# zikzak-z80-2.net
KiCad netlist of a schematic drawn in EAGLE
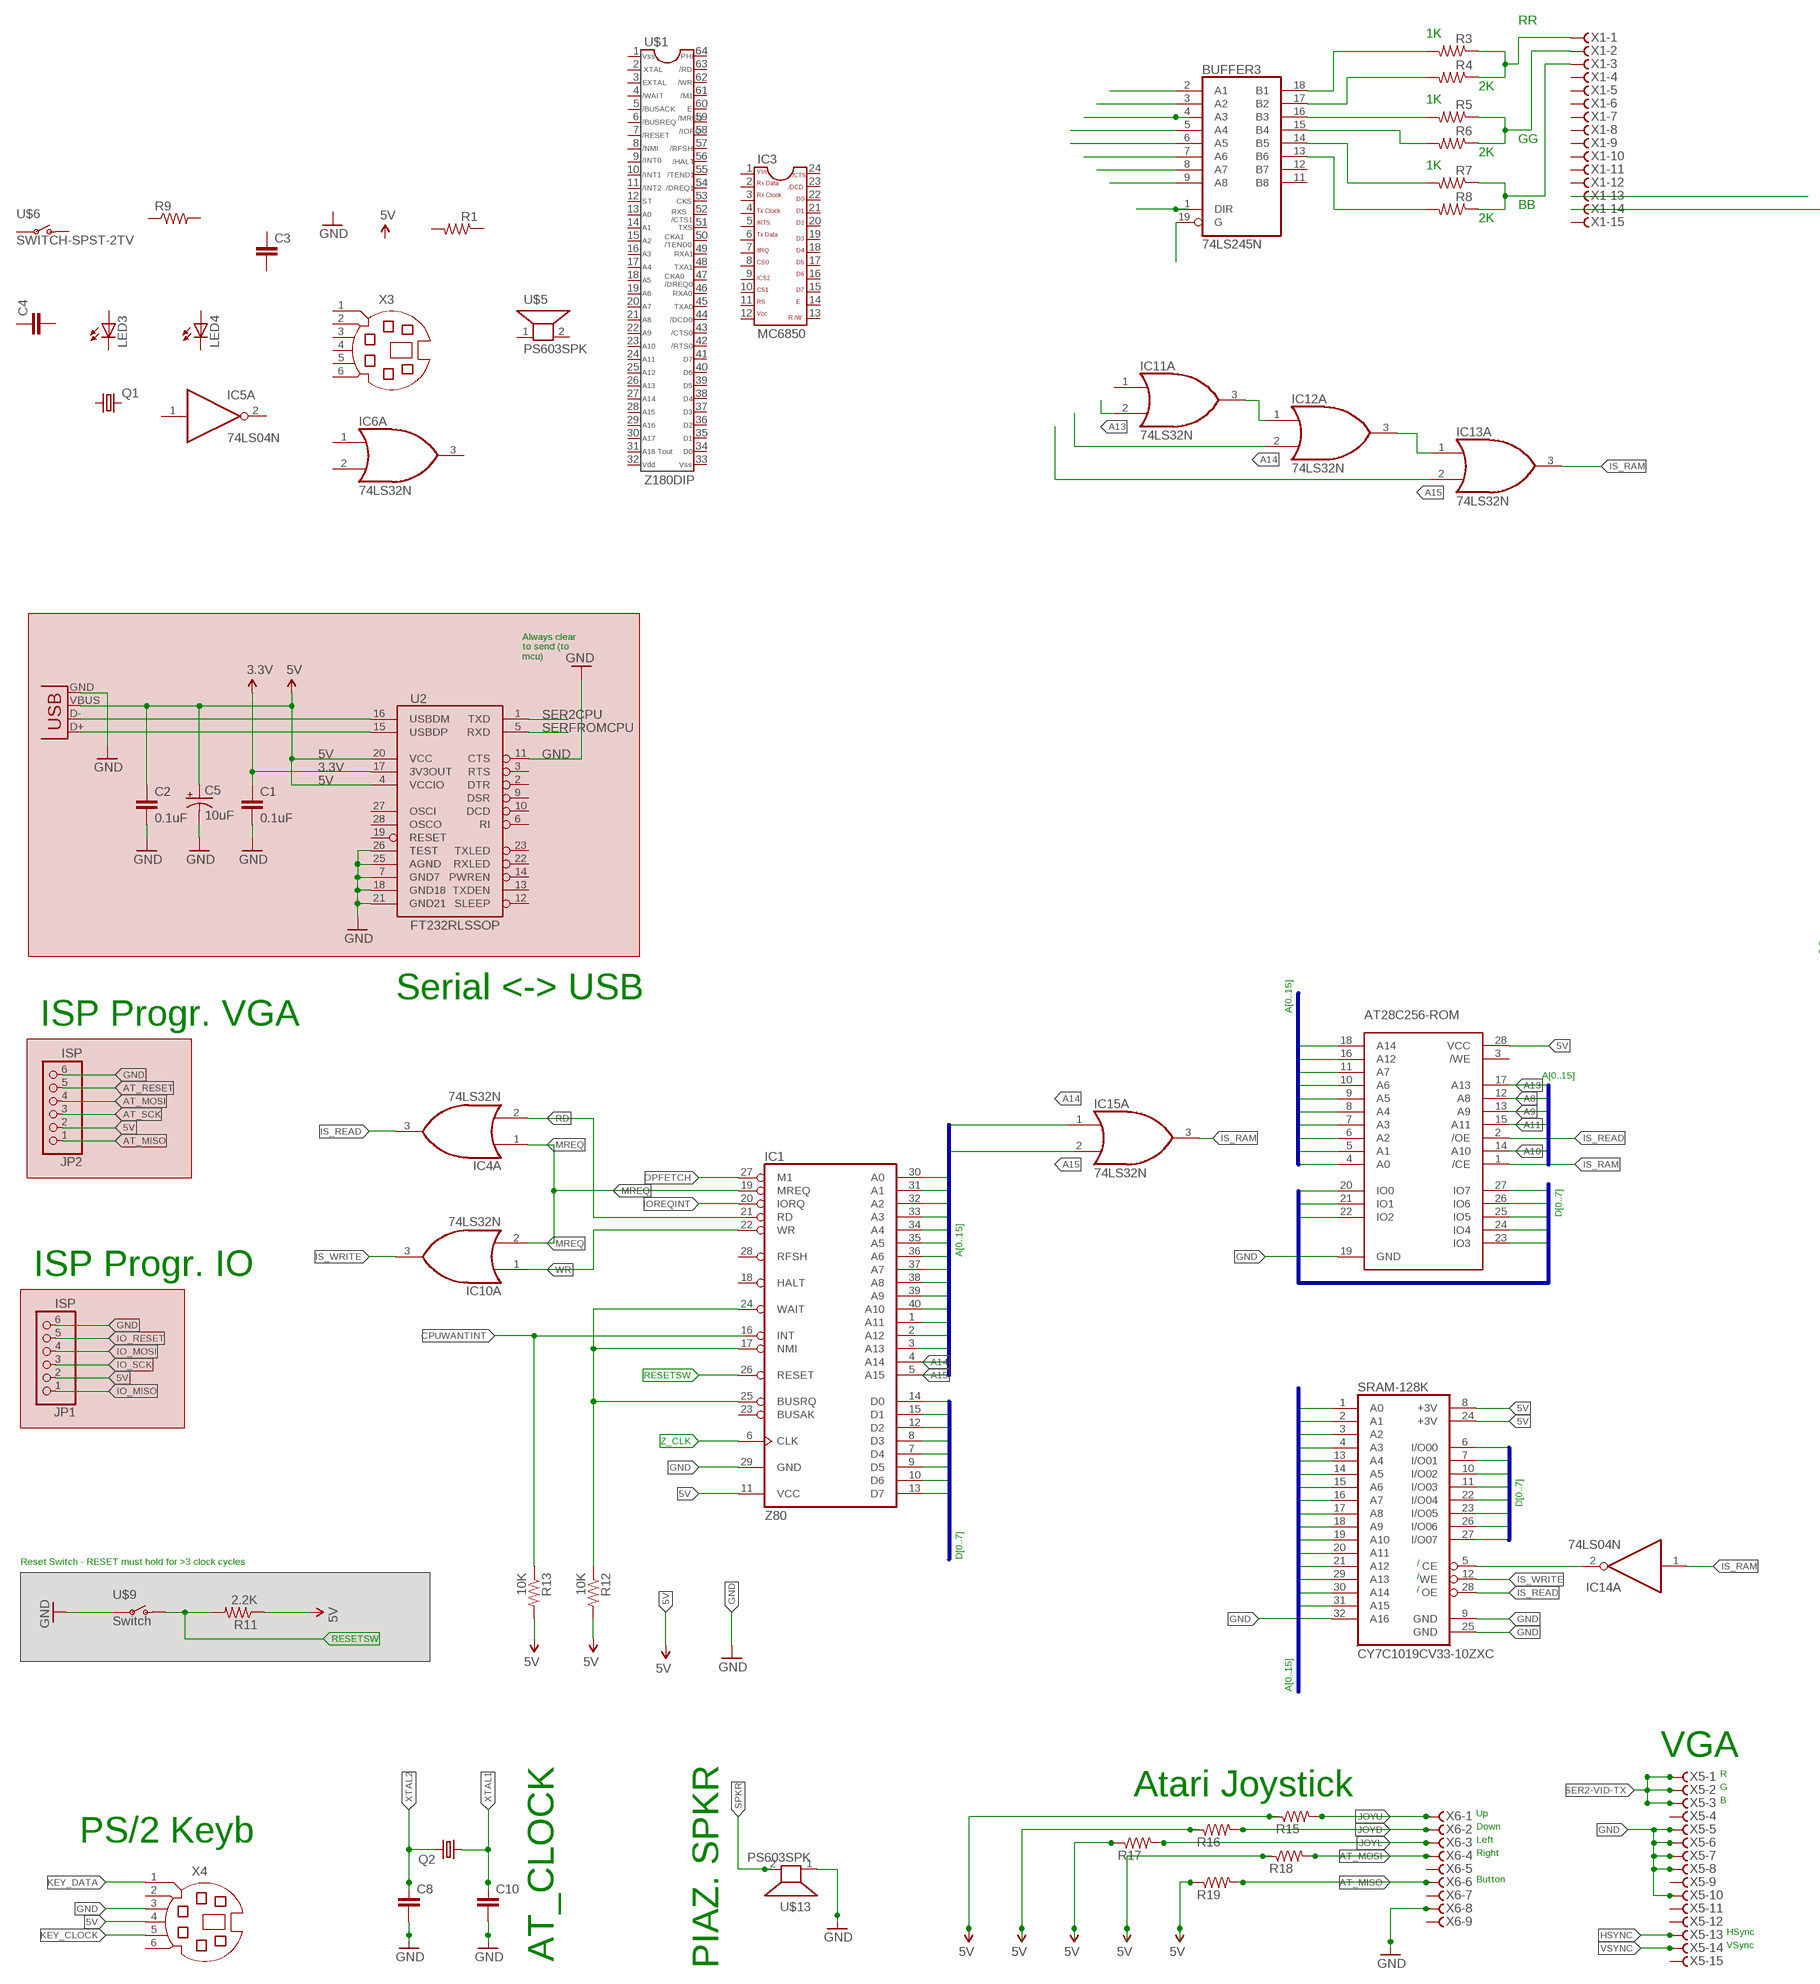
[diagram p0: schematic, sheet 1, part 1 of 2]
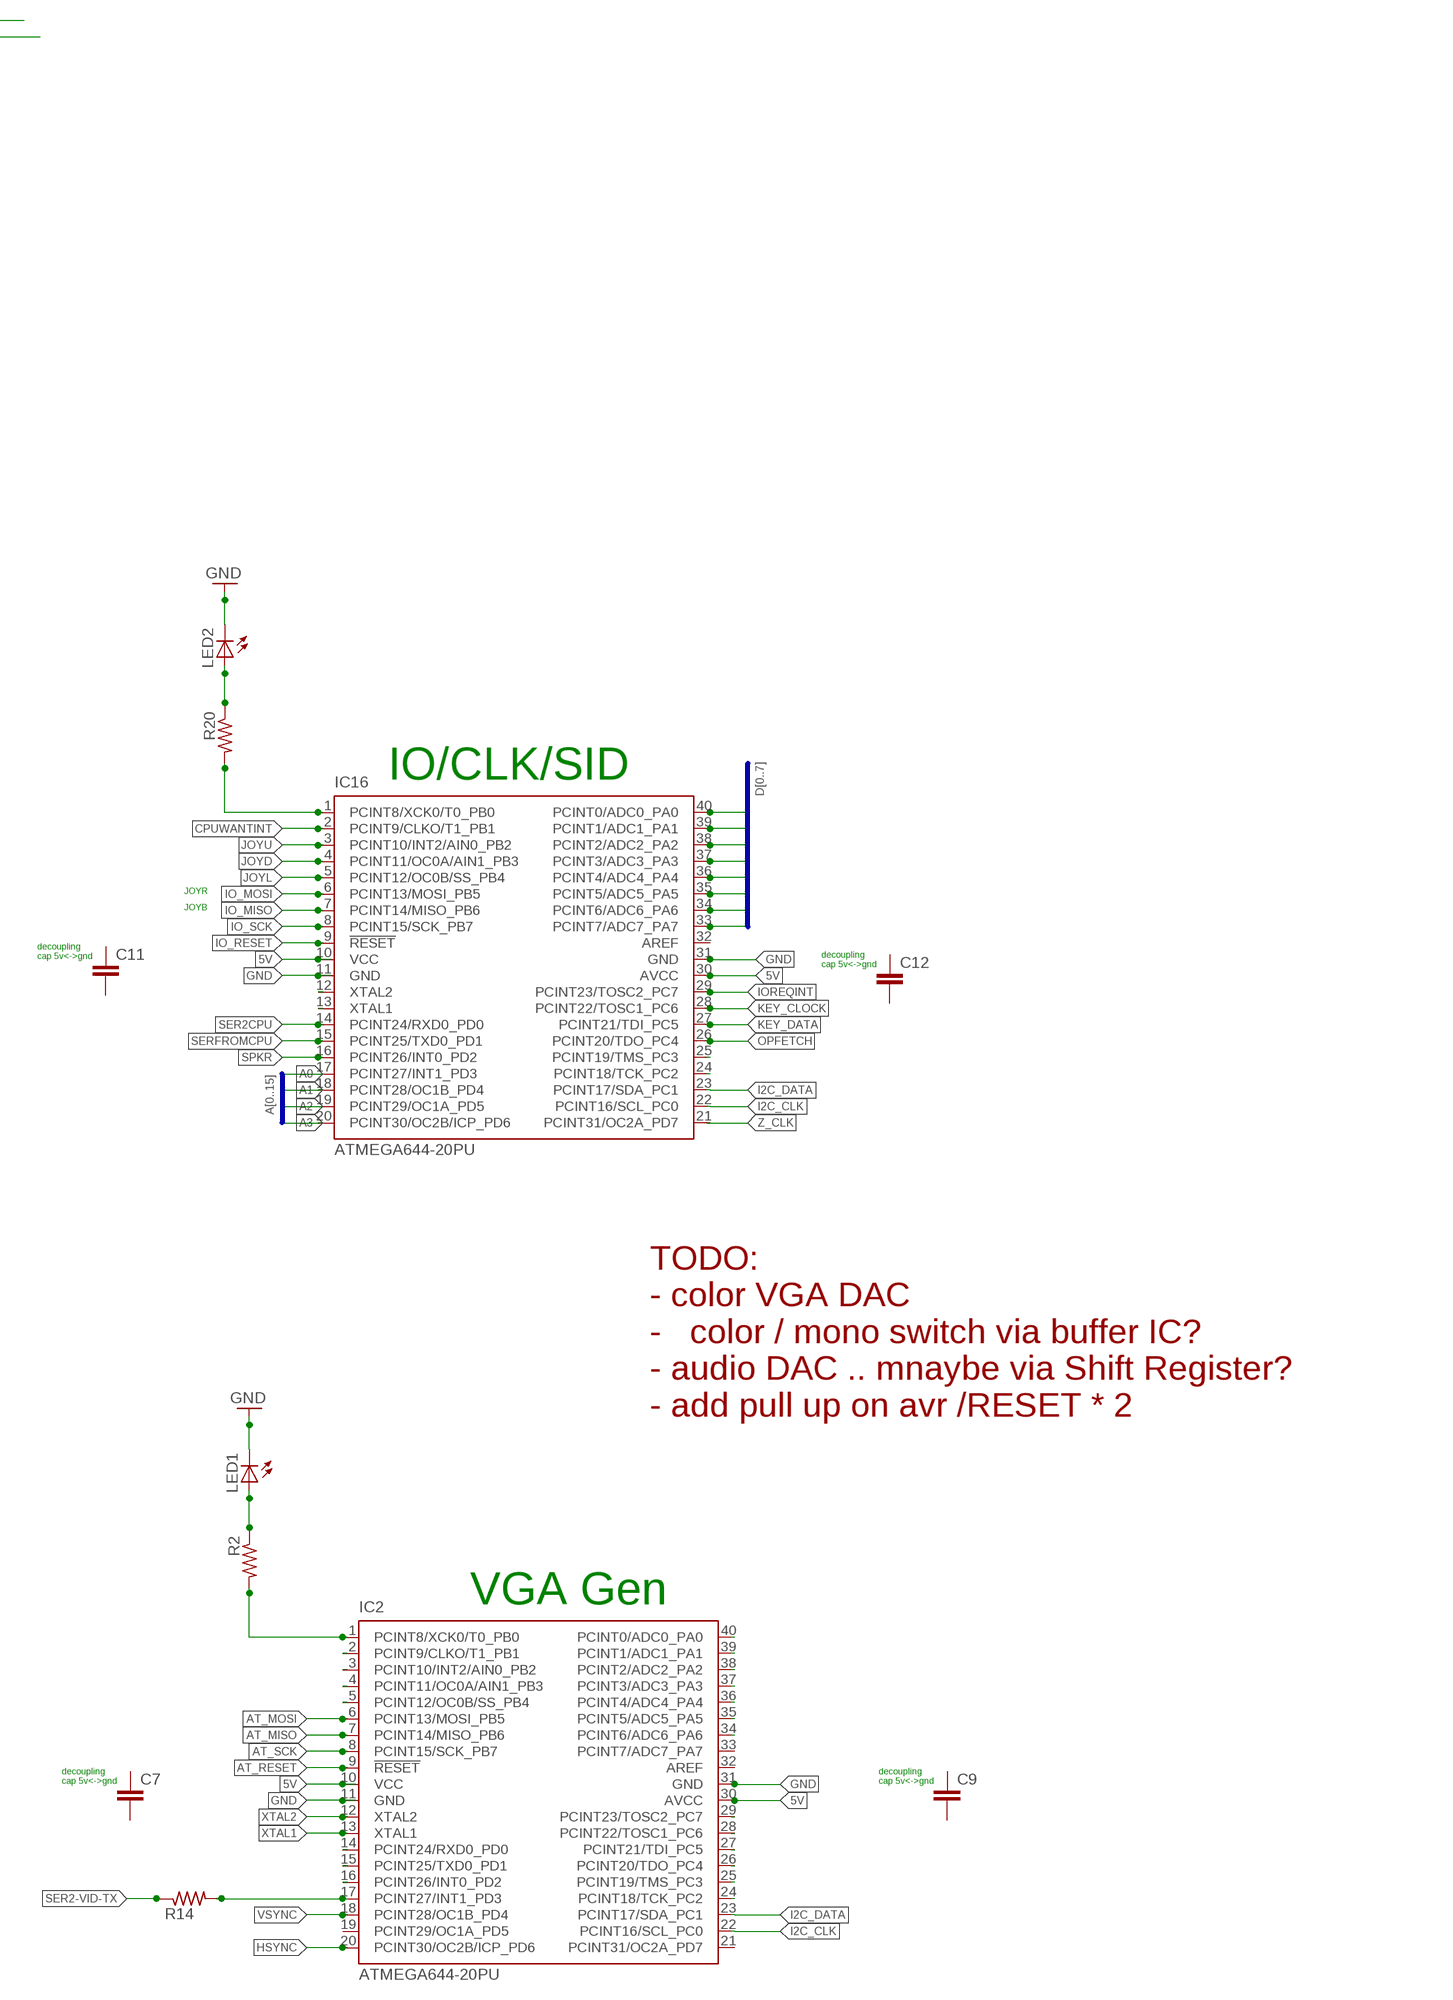
[diagram p1: schematic, sheet 1, part 2 of 2]

(export (version "E")
  (design (tool "Eeschema 10.0.6"))
  (components
    (comp (ref "AT28C256-ROM")
      (value "AT28C256")
      (footprint "eagle-import:DIL28-4")
      (libsource (lib "eagle-import") (part "AT28C256"))
    )
    (comp (ref "BUFFER3")
      (value "74LS245N")
      (footprint "eagle-import:DIL20")
      (libsource (lib "eagle-import") (part "74245NLS"))
    )
    (comp (ref "C1")
      (value "0.1uF")
      (footprint "eagle-import:0402-CAP")
      (libsource (lib "eagle-import") (part "CAP0402-CAP"))
    )
    (comp (ref "C2")
      (value "0.1uF")
      (footprint "eagle-import:0402-CAP")
      (libsource (lib "eagle-import") (part "CAP0402-CAP"))
    )
    (comp (ref "C3")
      (value "C-EU025-050X050")
      (footprint "eagle-import:C025-050X050")
      (libsource (lib "eagle-import") (part "C-EU025-050X050"))
    )
    (comp (ref "C4")
      (value "C-EUC0504")
      (footprint "eagle-import:C0504")
      (libsource (lib "eagle-import") (part "C-EUC0504"))
    )
    (comp (ref "C5")
      (value "10uF")
      (footprint "eagle-import:EIA3216")
      (libsource (lib "eagle-import") (part "CAP_POL1206"))
    )
    (comp (ref "C7")
      (value "C-EU025-050X050")
      (footprint "eagle-import:C025-050X050")
      (libsource (lib "eagle-import") (part "C-EU025-050X050"))
    )
    (comp (ref "C8")
      (value "C-EU025-050X050")
      (footprint "eagle-import:C025-050X050")
      (libsource (lib "eagle-import") (part "C-EU025-050X050"))
    )
    (comp (ref "C9")
      (value "C-EU025-050X050")
      (footprint "eagle-import:C025-050X050")
      (libsource (lib "eagle-import") (part "C-EU025-050X050"))
    )
    (comp (ref "C10")
      (value "C-EU025-050X050")
      (footprint "eagle-import:C025-050X050")
      (libsource (lib "eagle-import") (part "C-EU025-050X050"))
    )
    (comp (ref "C11")
      (value "C-EU025-050X050")
      (footprint "eagle-import:C025-050X050")
      (libsource (lib "eagle-import") (part "C-EU025-050X050"))
    )
    (comp (ref "C12")
      (value "C-EU025-050X050")
      (footprint "eagle-import:C025-050X050")
      (libsource (lib "eagle-import") (part "C-EU025-050X050"))
    )
    (comp (ref "IC1")
      (value "Z80")
      (footprint "eagle-import:DIL40")
      (libsource (lib "eagle-import") (part "Z80CPU"))
    )
    (comp (ref "IC2")
      (value "ATMEGA644-20PU")
      (footprint "eagle-import:DIL40")
      (libsource (lib "eagle-import") (part "ATMEGA644-PU20"))
    )
    (comp (ref "IC3")
      (value "MC6850")
      (footprint "eagle-import:DIL24-6")
      (libsource (lib "eagle-import") (part "MC6850-ACIA-6"))
    )
    (comp (ref "IC4")
      (value "74LS32N")
      (footprint "eagle-import:DIL14")
      (libsource (lib "eagle-import") (part "7432NLS"))
    )
    (comp (ref "IC5")
      (value "74LS04N")
      (footprint "eagle-import:DIL14")
      (libsource (lib "eagle-import") (part "7404NLS"))
    )
    (comp (ref "IC6")
      (value "74LS32N")
      (footprint "eagle-import:DIL14")
      (libsource (lib "eagle-import") (part "7432NLS"))
    )
    (comp (ref "IC10")
      (value "74LS32N")
      (footprint "eagle-import:DIL14")
      (libsource (lib "eagle-import") (part "7432NLS"))
    )
    (comp (ref "IC11")
      (value "74LS32N")
      (footprint "eagle-import:DIL14")
      (libsource (lib "eagle-import") (part "7432NLS"))
    )
    (comp (ref "IC12")
      (value "74LS32N")
      (footprint "eagle-import:DIL14")
      (libsource (lib "eagle-import") (part "7432NLS"))
    )
    (comp (ref "IC13")
      (value "74LS32N")
      (footprint "eagle-import:DIL14")
      (libsource (lib "eagle-import") (part "7432NLS"))
    )
    (comp (ref "IC14")
      (value "74LS04N")
      (footprint "eagle-import:DIL14")
      (libsource (lib "eagle-import") (part "7404NLS"))
    )
    (comp (ref "IC15")
      (value "74LS32N")
      (footprint "eagle-import:DIL14")
      (libsource (lib "eagle-import") (part "7432NLS"))
    )
    (comp (ref "IC16")
      (value "ATMEGA644-20PU")
      (footprint "eagle-import:DIL40")
      (libsource (lib "eagle-import") (part "ATMEGA644-PU20"))
    )
    (comp (ref "JP1")
      (value "ISP")
      (footprint "eagle-import:1X06")
      (libsource (lib "eagle-import") (part "PINHD-1X6"))
    )
    (comp (ref "JP2")
      (value "ISP")
      (footprint "eagle-import:1X06")
      (libsource (lib "eagle-import") (part "PINHD-1X6"))
    )
    (comp (ref "LED1")
      (value "LEDMINI-TOP")
      (footprint "eagle-import:OSRAM-MINI-TOP-LED")
      (libsource (lib "eagle-import") (part "LEDMINI-TOP"))
    )
    (comp (ref "LED2")
      (value "LEDMINI-TOP")
      (footprint "eagle-import:OSRAM-MINI-TOP-LED")
      (libsource (lib "eagle-import") (part "LEDMINI-TOP"))
    )
    (comp (ref "LED3")
      (value "LEDMINI-TOP")
      (footprint "eagle-import:OSRAM-MINI-TOP-LED")
      (libsource (lib "eagle-import") (part "LEDMINI-TOP"))
    )
    (comp (ref "LED4")
      (value "LEDMINI-TOP")
      (footprint "eagle-import:OSRAM-MINI-TOP-LED")
      (libsource (lib "eagle-import") (part "LEDMINI-TOP"))
    )
    (comp (ref "Q1")
      (value "CRYSTALHC49S")
      (footprint "eagle-import:HC49_S")
      (libsource (lib "eagle-import") (part "CRYSTALHC49S"))
    )
    (comp (ref "Q2")
      (value "CRYSTALHC49S")
      (footprint "eagle-import:HC49_S")
      (libsource (lib "eagle-import") (part "CRYSTALHC49S"))
    )
    (comp (ref "R1")
      (value "R-US_0204/2V")
      (footprint "eagle-import:0204V")
      (libsource (lib "eagle-import") (part "R-US_0204/2V"))
    )
    (comp (ref "R2")
      (value "R-US_0204/2V")
      (footprint "eagle-import:0204V")
      (libsource (lib "eagle-import") (part "R-US_0204/2V"))
    )
    (comp (ref "R3")
      (value "R-US_0204/2V")
      (footprint "eagle-import:0204V")
      (libsource (lib "eagle-import") (part "R-US_0204/2V"))
    )
    (comp (ref "R4")
      (value "R-US_0204/2V")
      (footprint "eagle-import:0204V")
      (libsource (lib "eagle-import") (part "R-US_0204/2V"))
    )
    (comp (ref "R5")
      (value "R-US_0204/2V")
      (footprint "eagle-import:0204V")
      (libsource (lib "eagle-import") (part "R-US_0204/2V"))
    )
    (comp (ref "R6")
      (value "R-US_0204/2V")
      (footprint "eagle-import:0204V")
      (libsource (lib "eagle-import") (part "R-US_0204/2V"))
    )
    (comp (ref "R7")
      (value "R-US_0204/2V")
      (footprint "eagle-import:0204V")
      (libsource (lib "eagle-import") (part "R-US_0204/2V"))
    )
    (comp (ref "R8")
      (value "R-US_0204/2V")
      (footprint "eagle-import:0204V")
      (libsource (lib "eagle-import") (part "R-US_0204/2V"))
    )
    (comp (ref "R9")
      (value "R-US_0204/7")
      (footprint "eagle-import:0204_7")
      (libsource (lib "eagle-import") (part "R-US_0204/7"))
    )
    (comp (ref "R11")
      (value "2.2K")
      (footprint "eagle-import:0204_7")
      (libsource (lib "eagle-import") (part "R-US_0204/7"))
    )
    (comp (ref "R12")
      (value "10K")
      (footprint "eagle-import:0204_7")
      (libsource (lib "eagle-import") (part "R-US_0204/7"))
    )
    (comp (ref "R13")
      (value "10K")
      (footprint "eagle-import:0204_7")
      (libsource (lib "eagle-import") (part "R-US_0204/7"))
    )
    (comp (ref "R14")
      (value "R-US_0204/2V")
      (footprint "eagle-import:0204V")
      (libsource (lib "eagle-import") (part "R-US_0204/2V"))
    )
    (comp (ref "R15")
      (value "R-US_0204/2V")
      (footprint "eagle-import:0204V")
      (libsource (lib "eagle-import") (part "R-US_0204/2V"))
    )
    (comp (ref "R16")
      (value "R-US_0204/2V")
      (footprint "eagle-import:0204V")
      (libsource (lib "eagle-import") (part "R-US_0204/2V"))
    )
    (comp (ref "R17")
      (value "R-US_0204/2V")
      (footprint "eagle-import:0204V")
      (libsource (lib "eagle-import") (part "R-US_0204/2V"))
    )
    (comp (ref "R18")
      (value "R-US_0204/2V")
      (footprint "eagle-import:0204V")
      (libsource (lib "eagle-import") (part "R-US_0204/2V"))
    )
    (comp (ref "R19")
      (value "R-US_0204/2V")
      (footprint "eagle-import:0204V")
      (libsource (lib "eagle-import") (part "R-US_0204/2V"))
    )
    (comp (ref "R20")
      (value "R-US_0204/2V")
      (footprint "eagle-import:0204V")
      (libsource (lib "eagle-import") (part "R-US_0204/2V"))
    )
    (comp (ref "SRAM-128K")
      (value "CY7C1019CV33-10ZXC")
      (footprint "eagle-import:TSOPII-32")
      (libsource (lib "eagle-import") (part "CY7C1019CV33ZXC-10"))
    )
    (comp (ref "U$1")
      (value "Z180DIP")
      (footprint "eagle-import:DIL64")
      (libsource (lib "eagle-import") (part "Z180DIP"))
    )
    (comp (ref "U$5")
      (value "PS603SPK")
      (footprint "eagle-import:PS603")
      (libsource (lib "eagle-import") (part "PS603SPK"))
    )
    (comp (ref "U$6")
      (value "SWITCH-SPST-2TV")
      (footprint "eagle-import:SWITCH-SPST-VERTICAL")
      (libsource (lib "eagle-import") (part "SWITCH-SPST-2TV"))
    )
    (comp (ref "U$9")
      (value "Switch")
      (footprint "eagle-import:SWITCH-SPST-VERTICAL")
      (libsource (lib "eagle-import") (part "SWITCH-SPST-2TV"))
    )
    (comp (ref "U$13")
      (value "PS603SPK")
      (footprint "eagle-import:PS603")
      (libsource (lib "eagle-import") (part "PS603SPK"))
    )
    (comp (ref "U2")
      (value "FT232RLSSOP")
      (footprint "eagle-import:SSOP28DB")
      (libsource (lib "eagle-import") (part "FT232RLSSOP"))
    )
    (comp (ref "X1")
      (value "F15HDVS")
      (footprint "eagle-import:HDF15V")
      (libsource (lib "eagle-import") (part "F15?SHDV"))
    )
    (comp (ref "X2")
      (value "USB-SMD-NS")
      (footprint "eagle-import:USB-MINIB-NOSTOP")
      (libsource (lib "eagle-import") (part "USB-SMD-NS"))
    )
    (comp (ref "X3")
      (value "MD06S")
      (footprint "eagle-import:MDIN06S")
      (libsource (lib "eagle-import") (part "MD06S"))
    )
    (comp (ref "X4")
      (value "MD06S")
      (footprint "eagle-import:MDIN06S")
      (libsource (lib "eagle-import") (part "MD06S"))
    )
    (comp (ref "X5")
      (value "F15HDVS")
      (footprint "eagle-import:HDF15V")
      (libsource (lib "eagle-import") (part "F15?SHDV"))
    )
    (comp (ref "X6")
      (value "F15HDVS")
      (footprint "eagle-import:HDF15V")
      (libsource (lib "eagle-import") (part "F15?SHDV"))
    )
  )
  (nets
    (net (code "1") (name "/A4") (class "Default")
      (node (ref "AT28C256-ROM") (pin "8") (pinfunction "A4_8") (pintype "input"))
      (node (ref "IC1") (pin "34") (pinfunction "A4_34") (pintype "output"))
      (node (ref "SRAM-128K") (pin "13") (pinfunction "A4_13") (pintype "input"))
    )
    (net (code "2") (name "/A5") (class "Default")
      (node (ref "AT28C256-ROM") (pin "9") (pinfunction "A5_9") (pintype "input"))
      (node (ref "IC1") (pin "35") (pinfunction "A5_35") (pintype "output"))
      (node (ref "SRAM-128K") (pin "14") (pinfunction "A5_14") (pintype "input"))
    )
    (net (code "3") (name "/A6") (class "Default")
      (node (ref "AT28C256-ROM") (pin "10") (pinfunction "A6_10") (pintype "input"))
      (node (ref "IC1") (pin "36") (pinfunction "A6_36") (pintype "output"))
      (node (ref "SRAM-128K") (pin "15") (pinfunction "A6_15") (pintype "input"))
    )
    (net (code "4") (name "/A7") (class "Default")
      (node (ref "AT28C256-ROM") (pin "11") (pinfunction "A7_11") (pintype "input"))
      (node (ref "IC1") (pin "37") (pinfunction "A7_37") (pintype "output"))
      (node (ref "SRAM-128K") (pin "16") (pinfunction "A7_16") (pintype "input"))
    )
    (net (code "5") (name "/A12") (class "Default")
      (node (ref "AT28C256-ROM") (pin "16") (pinfunction "A12_16") (pintype "input"))
      (node (ref "SRAM-128K") (pin "21") (pinfunction "A12_21") (pintype "input"))
    )
    (net (code "7") (name "/D0") (class "Default")
      (node (ref "AT28C256-ROM") (pin "20") (pinfunction "IO0_20") (pintype "bidirectional"))
      (node (ref "IC1") (pin "14") (pinfunction "D0_14") (pintype "bidirectional"))
      (node (ref "IC2") (pin "40") (pinfunction "PCINT0/ADC0_PA0_40") (pintype "bidirectional"))
      (node (ref "SRAM-128K") (pin "6") (pinfunction "I/O00_6") (pintype "bidirectional"))
    )
    (net (code "8") (name "/D1") (class "Default")
      (node (ref "AT28C256-ROM") (pin "21") (pinfunction "IO1_21") (pintype "bidirectional"))
      (node (ref "IC1") (pin "15") (pinfunction "D1_15") (pintype "bidirectional"))
      (node (ref "IC2") (pin "39") (pinfunction "PCINT1/ADC1_PA1_39") (pintype "bidirectional"))
      (node (ref "SRAM-128K") (pin "7") (pinfunction "I/O01_7") (pintype "bidirectional"))
    )
    (net (code "9") (name "/D2") (class "Default")
      (node (ref "AT28C256-ROM") (pin "22") (pinfunction "IO2_22") (pintype "bidirectional"))
      (node (ref "IC1") (pin "12") (pinfunction "D2_12") (pintype "bidirectional"))
      (node (ref "IC2") (pin "38") (pinfunction "PCINT2/ADC2_PA2_38") (pintype "bidirectional"))
      (node (ref "SRAM-128K") (pin "10") (pinfunction "I/O02_10") (pintype "bidirectional"))
    )
    (net (code "10") (name "/D3") (class "Default")
      (node (ref "AT28C256-ROM") (pin "23") (pinfunction "IO3_23") (pintype "bidirectional"))
      (node (ref "IC1") (pin "8") (pinfunction "D3_8") (pintype "bidirectional"))
      (node (ref "IC2") (pin "37") (pinfunction "PCINT3/ADC3_PA3_37") (pintype "bidirectional"))
      (node (ref "SRAM-128K") (pin "11") (pinfunction "I/O03_11") (pintype "bidirectional"))
    )
    (net (code "11") (name "/D4") (class "Default")
      (node (ref "AT28C256-ROM") (pin "24") (pinfunction "IO4_24") (pintype "bidirectional"))
      (node (ref "IC1") (pin "7") (pinfunction "D4_7") (pintype "bidirectional"))
      (node (ref "IC2") (pin "36") (pinfunction "PCINT4/ADC4_PA4_36") (pintype "bidirectional"))
      (node (ref "SRAM-128K") (pin "22") (pinfunction "I/O04_22") (pintype "bidirectional"))
    )
    (net (code "12") (name "/D5") (class "Default")
      (node (ref "AT28C256-ROM") (pin "25") (pinfunction "IO5_25") (pintype "bidirectional"))
      (node (ref "IC1") (pin "9") (pinfunction "D5_9") (pintype "bidirectional"))
      (node (ref "IC2") (pin "35") (pinfunction "PCINT5/ADC5_PA5_35") (pintype "bidirectional"))
      (node (ref "SRAM-128K") (pin "23") (pinfunction "I/O05_23") (pintype "bidirectional"))
    )
    (net (code "13") (name "/D6") (class "Default")
      (node (ref "AT28C256-ROM") (pin "26") (pinfunction "IO6_26") (pintype "bidirectional"))
      (node (ref "IC1") (pin "10") (pinfunction "D6_10") (pintype "bidirectional"))
      (node (ref "IC2") (pin "34") (pinfunction "PCINT6/ADC6_PA6_34") (pintype "bidirectional"))
      (node (ref "SRAM-128K") (pin "26") (pinfunction "I/O06_26") (pintype "bidirectional"))
    )
    (net (code "14") (name "/D7") (class "Default")
      (node (ref "AT28C256-ROM") (pin "27") (pinfunction "IO7_27") (pintype "bidirectional"))
      (node (ref "IC1") (pin "13") (pinfunction "D7_13") (pintype "bidirectional"))
      (node (ref "SRAM-128K") (pin "27") (pinfunction "I/O07_27") (pintype "bidirectional"))
    )
    (net (code "16") (name "3.3V") (class "Default")
      (node (ref "C1") (pin "1") (pinfunction "1_1") (pintype "passive"))
      (node (ref "U2") (pin "17") (pinfunction "3V3OUT_17") (pintype "output"))
    )
    (net (code "17") (name "5V") (class "Default")
      (node (ref "AT28C256-ROM") (pin "28") (pinfunction "VCC_28") (pintype "power_in"))
      (node (ref "C2") (pin "1") (pinfunction "1_1") (pintype "passive"))
      (node (ref "C5") (pin "A") (pinfunction "+_A") (pintype "passive"))
      (node (ref "IC1") (pin "11") (pinfunction "VCC_11") (pintype "power_in"))
      (node (ref "IC16") (pin "10") (pinfunction "VCC_10") (pintype "power_in"))
      (node (ref "IC16") (pin "30") (pinfunction "AVCC_30") (pintype "power_in"))
      (node (ref "IC2") (pin "10") (pinfunction "VCC_10") (pintype "power_in"))
      (node (ref "IC2") (pin "30") (pinfunction "AVCC_30") (pintype "power_in"))
      (node (ref "JP1") (pin "2") (pinfunction "2_2") (pintype "passive"))
      (node (ref "JP2") (pin "2") (pinfunction "2_2") (pintype "passive"))
      (node (ref "R11") (pin "1") (pinfunction "1_1") (pintype "passive"))
      (node (ref "R12") (pin "2") (pinfunction "2_2") (pintype "passive"))
      (node (ref "R13") (pin "2") (pinfunction "2_2") (pintype "passive"))
      (node (ref "R15") (pin "1") (pinfunction "1_1") (pintype "passive"))
      (node (ref "R16") (pin "1") (pinfunction "1_1") (pintype "passive"))
      (node (ref "R17") (pin "1") (pinfunction "1_1") (pintype "passive"))
      (node (ref "R18") (pin "1") (pinfunction "1_1") (pintype "passive"))
      (node (ref "R19") (pin "1") (pinfunction "1_1") (pintype "passive"))
      (node (ref "SRAM-128K") (pin "24") (pinfunction "+3V_24") (pintype "power_in"))
      (node (ref "SRAM-128K") (pin "8") (pinfunction "+3V_8") (pintype "power_in"))
      (node (ref "U2") (pin "20") (pinfunction "VCC_20") (pintype "power_in"))
      (node (ref "U2") (pin "4") (pinfunction "VCCIO_4") (pintype "power_in"))
      (node (ref "X2") (pin "VBUS") (pinfunction "VBUS_VBUS") (pintype "bidirectional"))
      (node (ref "X4") (pin "4") (pinfunction "4_4") (pintype "passive"))
    )
    (net (code "18") (name "A0") (class "Default")
      (node (ref "AT28C256-ROM") (pin "4") (pinfunction "A0_4") (pintype "input"))
      (node (ref "IC1") (pin "30") (pinfunction "A0_30") (pintype "output"))
      (node (ref "IC16") (pin "17") (pinfunction "PCINT27/INT1_PD3_17") (pintype "bidirectional"))
      (node (ref "SRAM-128K") (pin "1") (pinfunction "A0_1") (pintype "input"))
    )
    (net (code "19") (name "A1") (class "Default")
      (node (ref "AT28C256-ROM") (pin "5") (pinfunction "A1_5") (pintype "input"))
      (node (ref "IC1") (pin "31") (pinfunction "A1_31") (pintype "output"))
      (node (ref "IC16") (pin "18") (pinfunction "PCINT28/OC1B_PD4_18") (pintype "bidirectional"))
      (node (ref "SRAM-128K") (pin "2") (pinfunction "A1_2") (pintype "input"))
    )
    (net (code "20") (name "A2") (class "Default")
      (node (ref "AT28C256-ROM") (pin "6") (pinfunction "A2_6") (pintype "input"))
      (node (ref "IC1") (pin "32") (pinfunction "A2_32") (pintype "output"))
      (node (ref "IC16") (pin "24") (pinfunction "PCINT18/TCK_PC2_24") (pintype "bidirectional"))
      (node (ref "IC2") (pin "24") (pinfunction "PCINT18/TCK_PC2_24") (pintype "bidirectional"))
      (node (ref "SRAM-128K") (pin "3") (pinfunction "A2_3") (pintype "input"))
    )
    (net (code "21") (name "A3") (class "Default")
      (node (ref "AT28C256-ROM") (pin "7") (pinfunction "A3_7") (pintype "input"))
      (node (ref "IC1") (pin "33") (pinfunction "A3_33") (pintype "output"))
      (node (ref "IC16") (pin "20") (pinfunction "PCINT30/OC2B/ICP_PD6_20") (pintype "bidirectional"))
      (node (ref "IC16") (pin "25") (pinfunction "PCINT19/TMS_PC3_25") (pintype "bidirectional"))
      (node (ref "IC2") (pin "25") (pinfunction "PCINT19/TMS_PC3_25") (pintype "bidirectional"))
      (node (ref "SRAM-128K") (pin "4") (pinfunction "A3_4") (pintype "input"))
    )
    (net (code "22") (name "A8") (class "Default")
      (node (ref "AT28C256-ROM") (pin "12") (pinfunction "A8_12") (pintype "input"))
      (node (ref "IC1") (pin "38") (pinfunction "A8_38") (pintype "output"))
      (node (ref "SRAM-128K") (pin "17") (pinfunction "A8_17") (pintype "input"))
    )
    (net (code "23") (name "A9") (class "Default")
      (node (ref "AT28C256-ROM") (pin "13") (pinfunction "A9_13") (pintype "input"))
      (node (ref "IC1") (pin "39") (pinfunction "A9_39") (pintype "output"))
      (node (ref "SRAM-128K") (pin "18") (pinfunction "A9_18") (pintype "input"))
    )
    (net (code "24") (name "A10") (class "Default")
      (node (ref "AT28C256-ROM") (pin "14") (pinfunction "A10_14") (pintype "input"))
      (node (ref "IC1") (pin "40") (pinfunction "A10_40") (pintype "output"))
      (node (ref "SRAM-128K") (pin "19") (pinfunction "A10_19") (pintype "input"))
    )
    (net (code "25") (name "A11") (class "Default")
      (node (ref "AT28C256-ROM") (pin "15") (pinfunction "A11_15") (pintype "input"))
      (node (ref "IC1") (pin "1") (pinfunction "A11_1") (pintype "output"))
      (node (ref "SRAM-128K") (pin "20") (pinfunction "A11_20") (pintype "input"))
    )
    (net (code "26") (name "A13") (class "Default")
      (node (ref "AT28C256-ROM") (pin "17") (pinfunction "A13_17") (pintype "input"))
      (node (ref "IC11") (pin "2") (pinfunction "I1_2") (pintype "input"))
      (node (ref "SRAM-128K") (pin "29") (pinfunction "A13_29") (pintype "input"))
    )
    (net (code "27") (name "A14") (class "Default")
      (node (ref "AT28C256-ROM") (pin "18") (pinfunction "A14_18") (pintype "input"))
      (node (ref "IC1") (pin "4") (pinfunction "A14_4") (pintype "output"))
      (node (ref "IC12") (pin "2") (pinfunction "I1_2") (pintype "input"))
      (node (ref "IC15") (pin "1") (pinfunction "I0_1") (pintype "input"))
      (node (ref "SRAM-128K") (pin "30") (pinfunction "A14_30") (pintype "input"))
    )
    (net (code "28") (name "A15") (class "Default")
      (node (ref "IC1") (pin "5") (pinfunction "A15_5") (pintype "output"))
      (node (ref "IC13") (pin "2") (pinfunction "I1_2") (pintype "input"))
      (node (ref "SRAM-128K") (pin "31") (pinfunction "A15_31") (pintype "input"))
    )
    (net (code "29") (name "AT_MISO") (class "Default")
      (node (ref "IC2") (pin "7") (pinfunction "PCINT14/MISO_PB6_7") (pintype "bidirectional"))
      (node (ref "JP2") (pin "1") (pinfunction "1_1") (pintype "passive"))
      (node (ref "R19") (pin "2") (pinfunction "2_2") (pintype "passive"))
      (node (ref "X6") (pin "6") (pinfunction "F_6") (pintype "passive"))
    )
    (net (code "30") (name "AT_MOSI") (class "Default")
      (node (ref "IC2") (pin "6") (pinfunction "PCINT13/MOSI_PB5_6") (pintype "bidirectional"))
      (node (ref "JP2") (pin "4") (pinfunction "4_4") (pintype "passive"))
      (node (ref "R18") (pin "2") (pinfunction "2_2") (pintype "passive"))
      (node (ref "X6") (pin "4") (pinfunction "F_4") (pintype "passive"))
    )
    (net (code "31") (name "AT_RESET") (class "Default")
      (node (ref "IC2") (pin "9") (pinfunction "~{RESET}_9") (pintype "input"))
      (node (ref "JP2") (pin "5") (pinfunction "5_5") (pintype "passive"))
    )
    (net (code "32") (name "AT_SCK") (class "Default")
      (node (ref "IC2") (pin "8") (pinfunction "PCINT15/SCK_PB7_8") (pintype "bidirectional"))
      (node (ref "JP2") (pin "3") (pinfunction "3_3") (pintype "passive"))
    )
    (net (code "33") (name "CPUWANTINT") (class "Default")
      (node (ref "IC16") (pin "2") (pinfunction "PCINT9/CLKO/T1_PB1_2") (pintype "bidirectional"))
      (node (ref "IC2") (pin "2") (pinfunction "PCINT9/CLKO/T1_PB1_2") (pintype "bidirectional"))
      (node (ref "R13") (pin "1") (pinfunction "1_1") (pintype "passive"))
    )
    (net (code "34") (name "GND") (class "Default")
      (node (ref "AT28C256-ROM") (pin "19") (pinfunction "GND_19") (pintype "power_in"))
      (node (ref "C1") (pin "2") (pinfunction "2_2") (pintype "passive"))
      (node (ref "C10") (pin "2") (pinfunction "2_2") (pintype "passive"))
      (node (ref "C2") (pin "2") (pinfunction "2_2") (pintype "passive"))
      (node (ref "C5") (pin "C") (pinfunction "-_C") (pintype "passive"))
      (node (ref "C8") (pin "2") (pinfunction "2_2") (pintype "passive"))
      (node (ref "IC1") (pin "29") (pinfunction "GND_29") (pintype "power_in"))
      (node (ref "IC16") (pin "11") (pinfunction "GND_11") (pintype "power_in"))
      (node (ref "IC16") (pin "31") (pinfunction "GND_31") (pintype "power_in"))
      (node (ref "IC2") (pin "11") (pinfunction "GND_11") (pintype "power_in"))
      (node (ref "IC2") (pin "31") (pinfunction "GND_31") (pintype "power_in"))
      (node (ref "JP1") (pin "6") (pinfunction "6_6") (pintype "passive"))
      (node (ref "JP2") (pin "6") (pinfunction "6_6") (pintype "passive"))
      (node (ref "LED1") (pin "C") (pinfunction "C_C") (pintype "passive"))
      (node (ref "LED2") (pin "C") (pinfunction "C_C") (pintype "passive"))
      (node (ref "SRAM-128K") (pin "25") (pinfunction "GND_25") (pintype "power_in"))
      (node (ref "SRAM-128K") (pin "32") (pinfunction "A16_32") (pintype "input"))
      (node (ref "SRAM-128K") (pin "9") (pinfunction "GND_9") (pintype "power_in"))
      (node (ref "U$13") (pin "1") (pinfunction "1_1") (pintype "passive"))
      (node (ref "U$9") (pin "2") (pinfunction "P_2") (pintype "passive"))
      (node (ref "U2") (pin "11") (pinfunction "CTS_11") (pintype "input"))
      (node (ref "U2") (pin "18") (pinfunction "GND18_18") (pintype "power_in"))
      (node (ref "U2") (pin "21") (pinfunction "GND21_21") (pintype "power_in"))
      (node (ref "U2") (pin "25") (pinfunction "AGND_25") (pintype "power_in"))
      (node (ref "U2") (pin "26") (pinfunction "TEST_26") (pintype "input"))
      (node (ref "U2") (pin "7") (pinfunction "GND7_7") (pintype "power_in"))
      (node (ref "X2") (pin "GND") (pinfunction "GND_GND") (pintype "bidirectional"))
      (node (ref "X4") (pin "3") (pinfunction "3_3") (pintype "passive"))
      (node (ref "X5") (pin "10") (pinfunction "F_10") (pintype "passive"))
      (node (ref "X5") (pin "5") (pinfunction "F_5") (pintype "passive"))
      (node (ref "X5") (pin "6") (pinfunction "F_6") (pintype "passive"))
      (node (ref "X5") (pin "7") (pinfunction "F_7") (pintype "passive"))
      (node (ref "X5") (pin "8") (pinfunction "F_8") (pintype "passive"))
      (node (ref "X6") (pin "8") (pinfunction "F_8") (pintype "passive"))
    )
    (net (code "35") (name "HSYNC") (class "Default")
      (node (ref "IC2") (pin "20") (pinfunction "PCINT30/OC2B/ICP_PD6_20") (pintype "bidirectional"))
      (node (ref "X5") (pin "13") (pinfunction "F_13") (pintype "passive"))
    )
    (net (code "36") (name "I2C_CLK") (class "Default")
      (node (ref "IC16") (pin "22") (pinfunction "PCINT16/SCL_PC0_22") (pintype "bidirectional"))
      (node (ref "IC2") (pin "22") (pinfunction "PCINT16/SCL_PC0_22") (pintype "bidirectional"))
    )
    (net (code "37") (name "I2C_DATA") (class "Default")
      (node (ref "IC16") (pin "23") (pinfunction "PCINT17/SDA_PC1_23") (pintype "bidirectional"))
      (node (ref "IC2") (pin "23") (pinfunction "PCINT17/SDA_PC1_23") (pintype "bidirectional"))
    )
    (net (code "38") (name "IOREQINT") (class "Default")
      (node (ref "IC1") (pin "20") (pinfunction "IORQ_20") (pintype "output"))
      (node (ref "IC16") (pin "29") (pinfunction "PCINT23/TOSC2_PC7_29") (pintype "bidirectional"))
      (node (ref "IC2") (pin "29") (pinfunction "PCINT23/TOSC2_PC7_29") (pintype "bidirectional"))
    )
    (net (code "39") (name "IO_MISO") (class "Default")
      (node (ref "IC16") (pin "7") (pinfunction "PCINT14/MISO_PB6_7") (pintype "bidirectional"))
      (node (ref "JP1") (pin "1") (pinfunction "1_1") (pintype "passive"))
    )
    (net (code "40") (name "IO_MOSI") (class "Default")
      (node (ref "IC16") (pin "6") (pinfunction "PCINT13/MOSI_PB5_6") (pintype "bidirectional"))
      (node (ref "JP1") (pin "4") (pinfunction "4_4") (pintype "passive"))
    )
    (net (code "41") (name "IO_RESET") (class "Default")
      (node (ref "IC16") (pin "9") (pinfunction "~{RESET}_9") (pintype "input"))
      (node (ref "JP1") (pin "5") (pinfunction "5_5") (pintype "passive"))
    )
    (net (code "42") (name "IO_SCK") (class "Default")
      (node (ref "IC16") (pin "8") (pinfunction "PCINT15/SCK_PB7_8") (pintype "bidirectional"))
      (node (ref "JP1") (pin "3") (pinfunction "3_3") (pintype "passive"))
    )
    (net (code "43") (name "IS_RAM") (class "Default")
      (node (ref "AT28C256-ROM") (pin "1") (pinfunction "/CE_1") (pintype "input"))
      (node (ref "IC13") (pin "3") (pinfunction "O_3") (pintype "output"))
      (node (ref "IC14") (pin "1") (pinfunction "I_1") (pintype "input"))
      (node (ref "IC15") (pin "3") (pinfunction "O_3") (pintype "output"))
    )
    (net (code "44") (name "IS_READ") (class "Default")
      (node (ref "AT28C256-ROM") (pin "2") (pinfunction "/OE_2") (pintype "input"))
      (node (ref "IC4") (pin "3") (pinfunction "O_3") (pintype "output"))
      (node (ref "SRAM-128K") (pin "28") (pinfunction "OE_28") (pintype "input"))
    )
    (net (code "45") (name "IS_WRITE") (class "Default")
      (node (ref "IC10") (pin "3") (pinfunction "O_3") (pintype "output"))
      (node (ref "SRAM-128K") (pin "12") (pinfunction "WE_12") (pintype "input"))
    )
    (net (code "46") (name "JOYD") (class "Default")
      (node (ref "IC16") (pin "4") (pinfunction "PCINT11/OC0A/AIN1_PB3_4") (pintype "bidirectional"))
      (node (ref "IC2") (pin "4") (pinfunction "PCINT11/OC0A/AIN1_PB3_4") (pintype "bidirectional"))
      (node (ref "R16") (pin "2") (pinfunction "2_2") (pintype "passive"))
      (node (ref "X6") (pin "2") (pinfunction "F_2") (pintype "passive"))
    )
    (net (code "47") (name "JOYL") (class "Default")
      (node (ref "IC16") (pin "5") (pinfunction "PCINT12/OC0B/SS_PB4_5") (pintype "bidirectional"))
      (node (ref "IC2") (pin "5") (pinfunction "PCINT12/OC0B/SS_PB4_5") (pintype "bidirectional"))
      (node (ref "R17") (pin "2") (pinfunction "2_2") (pintype "passive"))
      (node (ref "X6") (pin "3") (pinfunction "F_3") (pintype "passive"))
    )
    (net (code "48") (name "JOYU") (class "Default")
      (node (ref "IC16") (pin "3") (pinfunction "PCINT10/INT2/AIN0_PB2_3") (pintype "bidirectional"))
      (node (ref "IC2") (pin "3") (pinfunction "PCINT10/INT2/AIN0_PB2_3") (pintype "bidirectional"))
      (node (ref "R15") (pin "2") (pinfunction "2_2") (pintype "passive"))
      (node (ref "X6") (pin "1") (pinfunction "F_1") (pintype "passive"))
    )
    (net (code "49") (name "KEY_CLOCK") (class "Default")
      (node (ref "IC16") (pin "28") (pinfunction "PCINT22/TOSC1_PC6_28") (pintype "bidirectional"))
      (node (ref "IC2") (pin "28") (pinfunction "PCINT22/TOSC1_PC6_28") (pintype "bidirectional"))
      (node (ref "X4") (pin "5") (pinfunction "5_5") (pintype "passive"))
    )
    (net (code "50") (name "KEY_DATA") (class "Default")
      (node (ref "IC16") (pin "27") (pinfunction "PCINT21/TDI_PC5_27") (pintype "bidirectional"))
      (node (ref "IC2") (pin "27") (pinfunction "PCINT21/TDI_PC5_27") (pintype "bidirectional"))
      (node (ref "X4") (pin "1") (pinfunction "1_1") (pintype "passive"))
    )
    (net (code "51") (name "MREQ") (class "Default")
      (node (ref "IC1") (pin "19") (pinfunction "MREQ_19") (pintype "output"))
      (node (ref "IC10") (pin "2") (pinfunction "I1_2") (pintype "input"))
      (node (ref "IC4") (pin "1") (pinfunction "I0_1") (pintype "input"))
    )
    (net (code "52") (name "Net-(BUFFER3A-B1)") (class "Default")
      (node (ref "BUFFER3") (pin "18") (pinfunction "B1_18") (pintype "bidirectional"))
      (node (ref "R3") (pin "2") (pinfunction "2_2") (pintype "passive"))
    )
    (net (code "53") (name "Net-(BUFFER3A-B2)") (class "Default")
      (node (ref "BUFFER3") (pin "17") (pinfunction "B2_17") (pintype "bidirectional"))
      (node (ref "R4") (pin "2") (pinfunction "2_2") (pintype "passive"))
    )
    (net (code "54") (name "Net-(BUFFER3A-B3)") (class "Default")
      (node (ref "BUFFER3") (pin "16") (pinfunction "B3_16") (pintype "bidirectional"))
      (node (ref "R5") (pin "2") (pinfunction "2_2") (pintype "passive"))
    )
    (net (code "55") (name "Net-(BUFFER3A-B4)") (class "Default")
      (node (ref "BUFFER3") (pin "15") (pinfunction "B4_15") (pintype "bidirectional"))
      (node (ref "R6") (pin "2") (pinfunction "2_2") (pintype "passive"))
    )
    (net (code "56") (name "Net-(BUFFER3A-B5)") (class "Default")
      (node (ref "BUFFER3") (pin "14") (pinfunction "B5_14") (pintype "bidirectional"))
      (node (ref "R7") (pin "2") (pinfunction "2_2") (pintype "passive"))
    )
    (net (code "57") (name "Net-(BUFFER3A-B6)") (class "Default")
      (node (ref "BUFFER3") (pin "13") (pinfunction "B6_13") (pintype "bidirectional"))
      (node (ref "R8") (pin "2") (pinfunction "2_2") (pintype "passive"))
    )
    (net (code "58") (name "Net-(IC1-BUSRQ)") (class "Default")
      (node (ref "IC1") (pin "17") (pinfunction "NMI_17") (pintype "input"))
      (node (ref "IC1") (pin "24") (pinfunction "WAIT_24") (pintype "input"))
      (node (ref "IC1") (pin "25") (pinfunction "BUSRQ_25") (pintype "input"))
      (node (ref "R12") (pin "1") (pinfunction "1_1") (pintype "passive"))
    )
    (net (code "59") (name "Net-(IC2-PCINT8{slash}XCK0{slash}T0_PB0)") (class "Default")
      (node (ref "IC2") (pin "1") (pinfunction "PCINT8/XCK0/T0_PB0_1") (pintype "bidirectional"))
      (node (ref "R2") (pin "2") (pinfunction "2_2") (pintype "passive"))
    )
    (net (code "60") (name "Net-(IC2-PCINT27{slash}INT1_PD3)") (class "Default")
      (node (ref "IC2") (pin "17") (pinfunction "PCINT27/INT1_PD3_17") (pintype "bidirectional"))
      (node (ref "R14") (pin "2") (pinfunction "2_2") (pintype "passive"))
    )
    (net (code "61") (name "Net-(IC11A-O)") (class "Default")
      (node (ref "IC11") (pin "3") (pinfunction "O_3") (pintype "output"))
      (node (ref "IC12") (pin "1") (pinfunction "I0_1") (pintype "input"))
    )
    (net (code "62") (name "Net-(IC12A-O)") (class "Default")
      (node (ref "IC12") (pin "3") (pinfunction "O_3") (pintype "output"))
      (node (ref "IC13") (pin "1") (pinfunction "I0_1") (pintype "input"))
    )
    (net (code "63") (name "Net-(IC14A-O)") (class "Default")
      (node (ref "IC14") (pin "2") (pinfunction "O_2") (pintype "output"))
      (node (ref "SRAM-128K") (pin "5") (pinfunction "CE_5") (pintype "bidirectional"))
    )
    (net (code "64") (name "Net-(IC16-PCINT8{slash}XCK0{slash}T0_PB0)") (class "Default")
      (node (ref "IC16") (pin "1") (pinfunction "PCINT8/XCK0/T0_PB0_1") (pintype "bidirectional"))
      (node (ref "R20") (pin "2") (pinfunction "2_2") (pintype "passive"))
    )
    (net (code "65") (name "Net-(LED1-PadA)") (class "Default")
      (node (ref "LED1") (pin "A") (pinfunction "A_A") (pintype "passive"))
      (node (ref "R2") (pin "1") (pinfunction "1_1") (pintype "passive"))
    )
    (net (code "66") (name "Net-(LED2-PadA)") (class "Default")
      (node (ref "LED2") (pin "A") (pinfunction "A_A") (pintype "passive"))
      (node (ref "R20") (pin "1") (pinfunction "1_1") (pintype "passive"))
    )
    (net (code "67") (name "Net-(U2-USBDM)") (class "Default")
      (node (ref "U2") (pin "16") (pinfunction "USBDM_16") (pintype "bidirectional"))
      (node (ref "X2") (pin "D-") (pinfunction "D-_D-") (pintype "bidirectional"))
    )
    (net (code "68") (name "Net-(U2-USBDP)") (class "Default")
      (node (ref "U2") (pin "15") (pinfunction "USBDP_15") (pintype "bidirectional"))
      (node (ref "X2") (pin "D+") (pinfunction "D+_D+") (pintype "bidirectional"))
    )
    (net (code "69") (name "Net-(X1A-F)") (class "Default")
      (node (ref "R3") (pin "1") (pinfunction "1_1") (pintype "passive"))
      (node (ref "R4") (pin "1") (pinfunction "1_1") (pintype "passive"))
      (node (ref "X1") (pin "1") (pinfunction "F_1") (pintype "passive"))
    )
    (net (code "70") (name "Net-(X1H-F)") (class "Default")
      (node (ref "R5") (pin "1") (pinfunction "1_1") (pintype "passive"))
      (node (ref "R6") (pin "1") (pinfunction "1_1") (pintype "passive"))
      (node (ref "X1") (pin "2") (pinfunction "F_2") (pintype "passive"))
    )
    (net (code "71") (name "Net-(X1I-F)") (class "Default")
      (node (ref "R7") (pin "1") (pinfunction "1_1") (pintype "passive"))
      (node (ref "R8") (pin "1") (pinfunction "1_1") (pintype "passive"))
      (node (ref "X1") (pin "3") (pinfunction "F_3") (pintype "passive"))
    )
    (net (code "72") (name "OPFETCH") (class "Default")
      (node (ref "IC1") (pin "27") (pinfunction "M1_27") (pintype "output"))
      (node (ref "IC16") (pin "26") (pinfunction "PCINT20/TDO_PC4_26") (pintype "bidirectional"))
      (node (ref "IC2") (pin "26") (pinfunction "PCINT20/TDO_PC4_26") (pintype "bidirectional"))
    )
    (net (code "73") (name "RD") (class "Default")
      (node (ref "IC1") (pin "21") (pinfunction "RD_21") (pintype "output"))
      (node (ref "IC4") (pin "2") (pinfunction "I1_2") (pintype "input"))
    )
    (net (code "74") (name "RESETSW") (class "Default")
      (node (ref "IC1") (pin "26") (pinfunction "RESET_26") (pintype "input"))
      (node (ref "R11") (pin "2") (pinfunction "2_2") (pintype "passive"))
      (node (ref "U$9") (pin "1") (pinfunction "O_1") (pintype "passive"))
    )
    (net (code "75") (name "SER2-VID-TX") (class "Default")
      (node (ref "R14") (pin "1") (pinfunction "1_1") (pintype "passive"))
      (node (ref "X5") (pin "1") (pinfunction "F_1") (pintype "passive"))
      (node (ref "X5") (pin "2") (pinfunction "F_2") (pintype "passive"))
      (node (ref "X5") (pin "3") (pinfunction "F_3") (pintype "passive"))
    )
    (net (code "76") (name "SER2CPU") (class "Default")
      (node (ref "IC16") (pin "14") (pinfunction "PCINT24/RXD0_PD0_14") (pintype "bidirectional"))
      (node (ref "IC2") (pin "14") (pinfunction "PCINT24/RXD0_PD0_14") (pintype "bidirectional"))
      (node (ref "U2") (pin "1") (pinfunction "TXD_1") (pintype "output"))
    )
    (net (code "77") (name "SERFROMCPU") (class "Default")
      (node (ref "IC16") (pin "15") (pinfunction "PCINT25/TXD0_PD1_15") (pintype "bidirectional"))
      (node (ref "IC2") (pin "15") (pinfunction "PCINT25/TXD0_PD1_15") (pintype "bidirectional"))
      (node (ref "U2") (pin "5") (pinfunction "RXD_5") (pintype "input"))
    )
    (net (code "78") (name "SPKR") (class "Default")
      (node (ref "IC16") (pin "16") (pinfunction "PCINT26/INT0_PD2_16") (pintype "bidirectional"))
      (node (ref "IC2") (pin "16") (pinfunction "PCINT26/INT0_PD2_16") (pintype "bidirectional"))
      (node (ref "U$13") (pin "2") (pinfunction "2_2") (pintype "passive"))
    )
    (net (code "79") (name "VSYNC") (class "Default")
      (node (ref "IC2") (pin "18") (pinfunction "PCINT28/OC1B_PD4_18") (pintype "bidirectional"))
      (node (ref "X5") (pin "14") (pinfunction "F_14") (pintype "passive"))
    )
    (net (code "80") (name "WR") (class "Default")
      (node (ref "IC1") (pin "22") (pinfunction "WR_22") (pintype "output"))
      (node (ref "IC10") (pin "1") (pinfunction "I0_1") (pintype "input"))
    )
    (net (code "81") (name "XTAL1") (class "Default")
      (node (ref "C10") (pin "1") (pinfunction "1_1") (pintype "passive"))
      (node (ref "IC16") (pin "13") (pinfunction "XTAL1_13") (pintype "input"))
      (node (ref "IC2") (pin "13") (pinfunction "XTAL1_13") (pintype "input"))
      (node (ref "Q2") (pin "1") (pinfunction "1_1") (pintype "passive"))
    )
    (net (code "82") (name "XTAL2") (class "Default")
      (node (ref "C8") (pin "1") (pinfunction "1_1") (pintype "passive"))
      (node (ref "IC16") (pin "12") (pinfunction "XTAL2_12") (pintype "output"))
      (node (ref "IC2") (pin "12") (pinfunction "XTAL2_12") (pintype "output"))
      (node (ref "Q2") (pin "2") (pinfunction "2_2") (pintype "passive"))
    )
    (net (code "83") (name "Z_CLK") (class "Default")
      (node (ref "IC1") (pin "6") (pinfunction "CLK_6") (pintype "input"))
    )
    (net (code "84") (name "unconnected-(AT28C256-ROM-{slash}WE-Pad3)") (class "Default")
      (node (ref "AT28C256-ROM") (pin "3") (pinfunction "/WE_3") (pintype "input"))
    )
    (net (code "85") (name "unconnected-(BUFFER3A-A1-Pad2)") (class "Default")
      (node (ref "BUFFER3") (pin "2") (pinfunction "A1_2") (pintype "bidirectional"))
    )
    (net (code "86") (name "unconnected-(BUFFER3A-A2-Pad3)") (class "Default")
      (node (ref "BUFFER3") (pin "3") (pinfunction "A2_3") (pintype "bidirectional"))
    )
    (net (code "87") (name "unconnected-(BUFFER3A-A3-Pad4)") (class "Default")
      (node (ref "BUFFER3") (pin "4") (pinfunction "A3_4") (pintype "bidirectional"))
    )
    (net (code "88") (name "unconnected-(BUFFER3A-A4-Pad5)") (class "Default")
      (node (ref "BUFFER3") (pin "5") (pinfunction "A4_5") (pintype "bidirectional"))
    )
    (net (code "89") (name "unconnected-(BUFFER3A-A5-Pad6)") (class "Default")
      (node (ref "BUFFER3") (pin "6") (pinfunction "A5_6") (pintype "bidirectional"))
    )
    (net (code "90") (name "unconnected-(BUFFER3A-A6-Pad7)") (class "Default")
      (node (ref "BUFFER3") (pin "7") (pinfunction "A6_7") (pintype "bidirectional"))
    )
    (net (code "91") (name "unconnected-(BUFFER3A-A7-Pad8)") (class "Default")
      (node (ref "BUFFER3") (pin "8") (pinfunction "A7_8") (pintype "bidirectional"))
    )
    (net (code "92") (name "unconnected-(BUFFER3A-A8-Pad9)") (class "Default")
      (node (ref "BUFFER3") (pin "9") (pinfunction "A8_9") (pintype "bidirectional"))
    )
    (net (code "93") (name "unconnected-(BUFFER3A-B7-Pad12)") (class "Default")
      (node (ref "BUFFER3") (pin "12") (pinfunction "B7_12") (pintype "bidirectional"))
    )
    (net (code "94") (name "unconnected-(BUFFER3A-B8-Pad11)") (class "Default")
      (node (ref "BUFFER3") (pin "11") (pinfunction "B8_11") (pintype "bidirectional"))
    )
    (net (code "95") (name "unconnected-(BUFFER3A-DIR-Pad1)") (class "Default")
      (node (ref "BUFFER3") (pin "1") (pinfunction "DIR_1") (pintype "input"))
    )
    (net (code "96") (name "unconnected-(BUFFER3A-G-Pad19)") (class "Default")
      (node (ref "BUFFER3") (pin "19") (pinfunction "G_19") (pintype "input"))
    )
    (net (code "97") (name "unconnected-(C3-Pad1)") (class "Default")
      (node (ref "C3") (pin "1") (pinfunction "1_1") (pintype "passive"))
    )
    (net (code "98") (name "unconnected-(C3-Pad2)") (class "Default")
      (node (ref "C3") (pin "2") (pinfunction "2_2") (pintype "passive"))
    )
    (net (code "99") (name "unconnected-(C4-Pad1)") (class "Default")
      (node (ref "C4") (pin "1") (pinfunction "1_1") (pintype "passive"))
    )
    (net (code "100") (name "unconnected-(C4-Pad2)") (class "Default")
      (node (ref "C4") (pin "2") (pinfunction "2_2") (pintype "passive"))
    )
    (net (code "101") (name "unconnected-(C7-Pad1)") (class "Default")
      (node (ref "C7") (pin "1") (pinfunction "1_1") (pintype "passive"))
    )
    (net (code "102") (name "unconnected-(C7-Pad2)") (class "Default")
      (node (ref "C7") (pin "2") (pinfunction "2_2") (pintype "passive"))
    )
    (net (code "103") (name "unconnected-(C9-Pad1)") (class "Default")
      (node (ref "C9") (pin "1") (pinfunction "1_1") (pintype "passive"))
    )
    (net (code "104") (name "unconnected-(C9-Pad2)") (class "Default")
      (node (ref "C9") (pin "2") (pinfunction "2_2") (pintype "passive"))
    )
    (net (code "105") (name "unconnected-(C11-Pad1)") (class "Default")
      (node (ref "C11") (pin "1") (pinfunction "1_1") (pintype "passive"))
    )
    (net (code "106") (name "unconnected-(C11-Pad2)") (class "Default")
      (node (ref "C11") (pin "2") (pinfunction "2_2") (pintype "passive"))
    )
    (net (code "107") (name "unconnected-(C12-Pad1)") (class "Default")
      (node (ref "C12") (pin "1") (pinfunction "1_1") (pintype "passive"))
    )
    (net (code "108") (name "unconnected-(C12-Pad2)") (class "Default")
      (node (ref "C12") (pin "2") (pinfunction "2_2") (pintype "passive"))
    )
    (net (code "109") (name "unconnected-(IC1-A12-Pad2)") (class "Default")
      (node (ref "IC1") (pin "2") (pinfunction "A12_2") (pintype "output"))
    )
    (net (code "110") (name "unconnected-(IC1-A13-Pad3)") (class "Default")
      (node (ref "IC1") (pin "3") (pinfunction "A13_3") (pintype "output"))
    )
    (net (code "111") (name "unconnected-(IC1-BUSAK-Pad23)") (class "Default")
      (node (ref "IC1") (pin "23") (pinfunction "BUSAK_23") (pintype "output"))
    )
    (net (code "112") (name "unconnected-(IC1-HALT-Pad18)") (class "Default")
      (node (ref "IC1") (pin "18") (pinfunction "HALT_18") (pintype "output"))
    )
    (net (code "113") (name "unconnected-(IC1-INT-Pad16)") (class "Default")
      (node (ref "IC1") (pin "16") (pinfunction "INT_16") (pintype "input"))
    )
    (net (code "114") (name "unconnected-(IC1-RFSH-Pad28)") (class "Default")
      (node (ref "IC1") (pin "28") (pinfunction "RFSH_28") (pintype "output"))
    )
    (net (code "115") (name "unconnected-(IC2-AREF-Pad32)") (class "Default")
      (node (ref "IC2") (pin "32") (pinfunction "AREF_32") (pintype "passive"))
    )
    (net (code "116") (name "unconnected-(IC2-PCINT7{slash}ADC7_PA7-Pad33)") (class "Default")
      (node (ref "IC2") (pin "33") (pinfunction "PCINT7/ADC7_PA7_33") (pintype "bidirectional"))
    )
    (net (code "117") (name "unconnected-(IC2-PCINT29{slash}OC1A_PD5-Pad19)") (class "Default")
      (node (ref "IC2") (pin "19") (pinfunction "PCINT29/OC1A_PD5_19") (pintype "bidirectional"))
    )
    (net (code "118") (name "unconnected-(IC2-PCINT31{slash}OC2A_PD7-Pad21)") (class "Default")
      (node (ref "IC2") (pin "21") (pinfunction "PCINT31/OC2A_PD7_21") (pintype "bidirectional"))
    )
    (net (code "119") (name "unconnected-(IC3-Pad1)") (class "Default")
      (node (ref "IC3") (pin "1") (pinfunction "1_1") (pintype "passive"))
    )
    (net (code "120") (name "unconnected-(IC3-Pad2)") (class "Default")
      (node (ref "IC3") (pin "2") (pinfunction "2_2") (pintype "passive"))
    )
    (net (code "121") (name "unconnected-(IC3-Pad3)") (class "Default")
      (node (ref "IC3") (pin "3") (pinfunction "3_3") (pintype "passive"))
    )
    (net (code "122") (name "unconnected-(IC3-Pad4)") (class "Default")
      (node (ref "IC3") (pin "4") (pinfunction "4_4") (pintype "passive"))
    )
    (net (code "123") (name "unconnected-(IC3-Pad5)") (class "Default")
      (node (ref "IC3") (pin "5") (pinfunction "5_5") (pintype "passive"))
    )
    (net (code "124") (name "unconnected-(IC3-Pad6)") (class "Default")
      (node (ref "IC3") (pin "6") (pinfunction "6_6") (pintype "passive"))
    )
    (net (code "125") (name "unconnected-(IC3-Pad7)") (class "Default")
      (node (ref "IC3") (pin "7") (pinfunction "7_7") (pintype "passive"))
    )
    (net (code "126") (name "unconnected-(IC3-Pad8)") (class "Default")
      (node (ref "IC3") (pin "8") (pinfunction "8_8") (pintype "passive"))
    )
    (net (code "127") (name "unconnected-(IC3-Pad9)") (class "Default")
      (node (ref "IC3") (pin "9") (pinfunction "9_9") (pintype "passive"))
    )
    (net (code "128") (name "unconnected-(IC3-Pad10)") (class "Default")
      (node (ref "IC3") (pin "10") (pinfunction "10_10") (pintype "passive"))
    )
    (net (code "129") (name "unconnected-(IC3-Pad11)") (class "Default")
      (node (ref "IC3") (pin "11") (pinfunction "11_11") (pintype "passive"))
    )
    (net (code "130") (name "unconnected-(IC3-Pad12)") (class "Default")
      (node (ref "IC3") (pin "12") (pinfunction "12_12") (pintype "passive"))
    )
    (net (code "131") (name "unconnected-(IC3-Pad13)") (class "Default")
      (node (ref "IC3") (pin "13") (pinfunction "13_13") (pintype "passive"))
    )
    (net (code "132") (name "unconnected-(IC3-Pad14)") (class "Default")
      (node (ref "IC3") (pin "14") (pinfunction "14_14") (pintype "passive"))
    )
    (net (code "133") (name "unconnected-(IC3-Pad15)") (class "Default")
      (node (ref "IC3") (pin "15") (pinfunction "15_15") (pintype "passive"))
    )
    (net (code "134") (name "unconnected-(IC3-Pad16)") (class "Default")
      (node (ref "IC3") (pin "16") (pinfunction "16_16") (pintype "passive"))
    )
    (net (code "135") (name "unconnected-(IC3-Pad17)") (class "Default")
      (node (ref "IC3") (pin "17") (pinfunction "17_17") (pintype "passive"))
    )
    (net (code "136") (name "unconnected-(IC3-Pad18)") (class "Default")
      (node (ref "IC3") (pin "18") (pinfunction "18_18") (pintype "passive"))
    )
    (net (code "137") (name "unconnected-(IC3-Pad19)") (class "Default")
      (node (ref "IC3") (pin "19") (pinfunction "19_19") (pintype "passive"))
    )
    (net (code "138") (name "unconnected-(IC3-Pad20)") (class "Default")
      (node (ref "IC3") (pin "20") (pinfunction "20_20") (pintype "passive"))
    )
    (net (code "139") (name "unconnected-(IC3-Pad21)") (class "Default")
      (node (ref "IC3") (pin "21") (pinfunction "21_21") (pintype "passive"))
    )
    (net (code "140") (name "unconnected-(IC3-Pad22)") (class "Default")
      (node (ref "IC3") (pin "22") (pinfunction "22_22") (pintype "passive"))
    )
    (net (code "141") (name "unconnected-(IC3-Pad23)") (class "Default")
      (node (ref "IC3") (pin "23") (pinfunction "23_23") (pintype "passive"))
    )
    (net (code "142") (name "unconnected-(IC3-Pad24)") (class "Default")
      (node (ref "IC3") (pin "24") (pinfunction "24_24") (pintype "passive"))
    )
    (net (code "143") (name "unconnected-(IC5A-I-Pad1)") (class "Default")
      (node (ref "IC5") (pin "1") (pinfunction "I_1") (pintype "input"))
    )
    (net (code "144") (name "unconnected-(IC5A-O-Pad2)") (class "Default")
      (node (ref "IC5") (pin "2") (pinfunction "O_2") (pintype "output"))
    )
    (net (code "145") (name "unconnected-(IC6A-I0-Pad1)") (class "Default")
      (node (ref "IC6") (pin "1") (pinfunction "I0_1") (pintype "input"))
    )
    (net (code "146") (name "unconnected-(IC6A-I1-Pad2)") (class "Default")
      (node (ref "IC6") (pin "2") (pinfunction "I1_2") (pintype "input"))
    )
    (net (code "147") (name "unconnected-(IC6A-O-Pad3)") (class "Default")
      (node (ref "IC6") (pin "3") (pinfunction "O_3") (pintype "output"))
    )
    (net (code "148") (name "unconnected-(IC11A-I0-Pad1)") (class "Default")
      (node (ref "IC11") (pin "1") (pinfunction "I0_1") (pintype "input"))
    )
    (net (code "149") (name "unconnected-(IC15A-I1-Pad2)") (class "Default")
      (node (ref "IC15") (pin "2") (pinfunction "I1_2") (pintype "input"))
    )
    (net (code "150") (name "unconnected-(IC16-AREF-Pad32)") (class "Default")
      (node (ref "IC16") (pin "32") (pinfunction "AREF_32") (pintype "passive"))
    )
    (net (code "151") (name "unconnected-(IC16-PCINT0{slash}ADC0_PA0-Pad40)") (class "Default")
      (node (ref "IC16") (pin "40") (pinfunction "PCINT0/ADC0_PA0_40") (pintype "bidirectional"))
    )
    (net (code "152") (name "unconnected-(IC16-PCINT1{slash}ADC1_PA1-Pad39)") (class "Default")
      (node (ref "IC16") (pin "39") (pinfunction "PCINT1/ADC1_PA1_39") (pintype "bidirectional"))
    )
    (net (code "153") (name "unconnected-(IC16-PCINT2{slash}ADC2_PA2-Pad38)") (class "Default")
      (node (ref "IC16") (pin "38") (pinfunction "PCINT2/ADC2_PA2_38") (pintype "bidirectional"))
    )
    (net (code "154") (name "unconnected-(IC16-PCINT3{slash}ADC3_PA3-Pad37)") (class "Default")
      (node (ref "IC16") (pin "37") (pinfunction "PCINT3/ADC3_PA3_37") (pintype "bidirectional"))
    )
    (net (code "155") (name "unconnected-(IC16-PCINT4{slash}ADC4_PA4-Pad36)") (class "Default")
      (node (ref "IC16") (pin "36") (pinfunction "PCINT4/ADC4_PA4_36") (pintype "bidirectional"))
    )
    (net (code "156") (name "unconnected-(IC16-PCINT5{slash}ADC5_PA5-Pad35)") (class "Default")
      (node (ref "IC16") (pin "35") (pinfunction "PCINT5/ADC5_PA5_35") (pintype "bidirectional"))
    )
    (net (code "157") (name "unconnected-(IC16-PCINT6{slash}ADC6_PA6-Pad34)") (class "Default")
      (node (ref "IC16") (pin "34") (pinfunction "PCINT6/ADC6_PA6_34") (pintype "bidirectional"))
    )
    (net (code "158") (name "unconnected-(IC16-PCINT7{slash}ADC7_PA7-Pad33)") (class "Default")
      (node (ref "IC16") (pin "33") (pinfunction "PCINT7/ADC7_PA7_33") (pintype "bidirectional"))
    )
    (net (code "159") (name "unconnected-(IC16-PCINT29{slash}OC1A_PD5-Pad19)") (class "Default")
      (node (ref "IC16") (pin "19") (pinfunction "PCINT29/OC1A_PD5_19") (pintype "bidirectional"))
    )
    (net (code "160") (name "unconnected-(IC16-PCINT31{slash}OC2A_PD7-Pad21)") (class "Default")
      (node (ref "IC16") (pin "21") (pinfunction "PCINT31/OC2A_PD7_21") (pintype "bidirectional"))
    )
    (net (code "161") (name "unconnected-(LED3-PadA)") (class "Default")
      (node (ref "LED3") (pin "A") (pinfunction "A_A") (pintype "passive"))
    )
    (net (code "162") (name "unconnected-(LED3-PadC)") (class "Default")
      (node (ref "LED3") (pin "C") (pinfunction "C_C") (pintype "passive"))
    )
    (net (code "163") (name "unconnected-(LED4-PadA)") (class "Default")
      (node (ref "LED4") (pin "A") (pinfunction "A_A") (pintype "passive"))
    )
    (net (code "164") (name "unconnected-(LED4-PadC)") (class "Default")
      (node (ref "LED4") (pin "C") (pinfunction "C_C") (pintype "passive"))
    )
    (net (code "165") (name "unconnected-(Q1-Pad1)") (class "Default")
      (node (ref "Q1") (pin "1") (pinfunction "1_1") (pintype "passive"))
    )
    (net (code "166") (name "unconnected-(Q1-Pad2)") (class "Default")
      (node (ref "Q1") (pin "2") (pinfunction "2_2") (pintype "passive"))
    )
    (net (code "167") (name "unconnected-(R1-Pad1)") (class "Default")
      (node (ref "R1") (pin "1") (pinfunction "1_1") (pintype "passive"))
    )
    (net (code "168") (name "unconnected-(R1-Pad2)") (class "Default")
      (node (ref "R1") (pin "2") (pinfunction "2_2") (pintype "passive"))
    )
    (net (code "169") (name "unconnected-(R9-Pad1)") (class "Default")
      (node (ref "R9") (pin "1") (pinfunction "1_1") (pintype "passive"))
    )
    (net (code "170") (name "unconnected-(R9-Pad2)") (class "Default")
      (node (ref "R9") (pin "2") (pinfunction "2_2") (pintype "passive"))
    )
    (net (code "171") (name "unconnected-(U$1-PHI-Pad64)") (class "Default")
      (node (ref "U$1") (pin "64") (pinfunction "PHI_64") (pintype "passive"))
    )
    (net (code "172") (name "unconnected-(U$1-Pad3)") (class "Default")
      (node (ref "U$1") (pin "3") (pinfunction "3_3") (pintype "passive"))
    )
    (net (code "173") (name "unconnected-(U$1-Pad4)") (class "Default")
      (node (ref "U$1") (pin "4") (pinfunction "4_4") (pintype "passive"))
    )
    (net (code "174") (name "unconnected-(U$1-Pad5)") (class "Default")
      (node (ref "U$1") (pin "5") (pinfunction "5_5") (pintype "passive"))
    )
    (net (code "175") (name "unconnected-(U$1-Pad6)") (class "Default")
      (node (ref "U$1") (pin "6") (pinfunction "6_6") (pintype "passive"))
    )
    (net (code "176") (name "unconnected-(U$1-Pad7)") (class "Default")
      (node (ref "U$1") (pin "7") (pinfunction "7_7") (pintype "passive"))
    )
    (net (code "177") (name "unconnected-(U$1-Pad8)") (class "Default")
      (node (ref "U$1") (pin "8") (pinfunction "8_8") (pintype "passive"))
    )
    (net (code "178") (name "unconnected-(U$1-Pad9)") (class "Default")
      (node (ref "U$1") (pin "9") (pinfunction "9_9") (pintype "passive"))
    )
    (net (code "179") (name "unconnected-(U$1-Pad10)") (class "Default")
      (node (ref "U$1") (pin "10") (pinfunction "10_10") (pintype "passive"))
    )
    (net (code "180") (name "unconnected-(U$1-Pad11)") (class "Default")
      (node (ref "U$1") (pin "11") (pinfunction "11_11") (pintype "passive"))
    )
    (net (code "181") (name "unconnected-(U$1-Pad12)") (class "Default")
      (node (ref "U$1") (pin "12") (pinfunction "12_12") (pintype "passive"))
    )
    (net (code "182") (name "unconnected-(U$1-Pad13)") (class "Default")
      (node (ref "U$1") (pin "13") (pinfunction "13_13") (pintype "passive"))
    )
    (net (code "183") (name "unconnected-(U$1-Pad14)") (class "Default")
      (node (ref "U$1") (pin "14") (pinfunction "14_14") (pintype "passive"))
    )
    (net (code "184") (name "unconnected-(U$1-Pad15)") (class "Default")
      (node (ref "U$1") (pin "15") (pinfunction "15_15") (pintype "passive"))
    )
    (net (code "185") (name "unconnected-(U$1-Pad16)") (class "Default")
      (node (ref "U$1") (pin "16") (pinfunction "16_16") (pintype "passive"))
    )
    (net (code "186") (name "unconnected-(U$1-Pad17)") (class "Default")
      (node (ref "U$1") (pin "17") (pinfunction "17_17") (pintype "passive"))
    )
    (net (code "187") (name "unconnected-(U$1-Pad18)") (class "Default")
      (node (ref "U$1") (pin "18") (pinfunction "18_18") (pintype "passive"))
    )
    (net (code "188") (name "unconnected-(U$1-Pad19)") (class "Default")
      (node (ref "U$1") (pin "19") (pinfunction "19_19") (pintype "passive"))
    )
    (net (code "189") (name "unconnected-(U$1-Pad20)") (class "Default")
      (node (ref "U$1") (pin "20") (pinfunction "20_20") (pintype "passive"))
    )
    (net (code "190") (name "unconnected-(U$1-Pad21)") (class "Default")
      (node (ref "U$1") (pin "21") (pinfunction "21_21") (pintype "passive"))
    )
    (net (code "191") (name "unconnected-(U$1-Pad22)") (class "Default")
      (node (ref "U$1") (pin "22") (pinfunction "22_22") (pintype "passive"))
    )
    (net (code "192") (name "unconnected-(U$1-Pad23)") (class "Default")
      (node (ref "U$1") (pin "23") (pinfunction "23_23") (pintype "passive"))
    )
    (net (code "193") (name "unconnected-(U$1-Pad24)") (class "Default")
      (node (ref "U$1") (pin "24") (pinfunction "24_24") (pintype "passive"))
    )
    (net (code "194") (name "unconnected-(U$1-Pad25)") (class "Default")
      (node (ref "U$1") (pin "25") (pinfunction "25_25") (pintype "passive"))
    )
    (net (code "195") (name "unconnected-(U$1-Pad26)") (class "Default")
      (node (ref "U$1") (pin "26") (pinfunction "26_26") (pintype "passive"))
    )
    (net (code "196") (name "unconnected-(U$1-Pad27)") (class "Default")
      (node (ref "U$1") (pin "27") (pinfunction "27_27") (pintype "passive"))
    )
    (net (code "197") (name "unconnected-(U$1-Pad28)") (class "Default")
      (node (ref "U$1") (pin "28") (pinfunction "28_28") (pintype "passive"))
    )
    (net (code "198") (name "unconnected-(U$1-Pad29)") (class "Default")
      (node (ref "U$1") (pin "29") (pinfunction "29_29") (pintype "passive"))
    )
    (net (code "199") (name "unconnected-(U$1-Pad30)") (class "Default")
      (node (ref "U$1") (pin "30") (pinfunction "30_30") (pintype "passive"))
    )
    (net (code "200") (name "unconnected-(U$1-Pad31)") (class "Default")
      (node (ref "U$1") (pin "31") (pinfunction "31_31") (pintype "passive"))
    )
    (net (code "201") (name "unconnected-(U$1-Pad32)") (class "Default")
      (node (ref "U$1") (pin "32") (pinfunction "32_32") (pintype "passive"))
    )
    (net (code "202") (name "unconnected-(U$1-Pad33)") (class "Default")
      (node (ref "U$1") (pin "33") (pinfunction "33_33") (pintype "passive"))
    )
    (net (code "203") (name "unconnected-(U$1-Pad34)") (class "Default")
      (node (ref "U$1") (pin "34") (pinfunction "34_34") (pintype "passive"))
    )
    (net (code "204") (name "unconnected-(U$1-Pad35)") (class "Default")
      (node (ref "U$1") (pin "35") (pinfunction "35_35") (pintype "passive"))
    )
    (net (code "205") (name "unconnected-(U$1-Pad36)") (class "Default")
      (node (ref "U$1") (pin "36") (pinfunction "36_36") (pintype "passive"))
    )
    (net (code "206") (name "unconnected-(U$1-Pad37)") (class "Default")
      (node (ref "U$1") (pin "37") (pinfunction "37_37") (pintype "passive"))
    )
    (net (code "207") (name "unconnected-(U$1-Pad38)") (class "Default")
      (node (ref "U$1") (pin "38") (pinfunction "38_38") (pintype "passive"))
    )
    (net (code "208") (name "unconnected-(U$1-Pad39)") (class "Default")
      (node (ref "U$1") (pin "39") (pinfunction "39_39") (pintype "passive"))
    )
    (net (code "209") (name "unconnected-(U$1-Pad40)") (class "Default")
      (node (ref "U$1") (pin "40") (pinfunction "40_40") (pintype "passive"))
    )
    (net (code "210") (name "unconnected-(U$1-Pad41)") (class "Default")
      (node (ref "U$1") (pin "41") (pinfunction "41_41") (pintype "passive"))
    )
    (net (code "211") (name "unconnected-(U$1-Pad42)") (class "Default")
      (node (ref "U$1") (pin "42") (pinfunction "42_42") (pintype "passive"))
    )
    (net (code "212") (name "unconnected-(U$1-Pad43)") (class "Default")
      (node (ref "U$1") (pin "43") (pinfunction "43_43") (pintype "passive"))
    )
    (net (code "213") (name "unconnected-(U$1-Pad44)") (class "Default")
      (node (ref "U$1") (pin "44") (pinfunction "44_44") (pintype "passive"))
    )
    (net (code "214") (name "unconnected-(U$1-Pad45)") (class "Default")
      (node (ref "U$1") (pin "45") (pinfunction "45_45") (pintype "passive"))
    )
    (net (code "215") (name "unconnected-(U$1-Pad46)") (class "Default")
      (node (ref "U$1") (pin "46") (pinfunction "46_46") (pintype "passive"))
    )
    (net (code "216") (name "unconnected-(U$1-Pad47)") (class "Default")
      (node (ref "U$1") (pin "47") (pinfunction "47_47") (pintype "passive"))
    )
    (net (code "217") (name "unconnected-(U$1-Pad48)") (class "Default")
      (node (ref "U$1") (pin "48") (pinfunction "48_48") (pintype "passive"))
    )
    (net (code "218") (name "unconnected-(U$1-Pad49)") (class "Default")
      (node (ref "U$1") (pin "49") (pinfunction "49_49") (pintype "passive"))
    )
    (net (code "219") (name "unconnected-(U$1-Pad50)") (class "Default")
      (node (ref "U$1") (pin "50") (pinfunction "50_50") (pintype "passive"))
    )
    (net (code "220") (name "unconnected-(U$1-Pad51)") (class "Default")
      (node (ref "U$1") (pin "51") (pinfunction "51_51") (pintype "passive"))
    )
    (net (code "221") (name "unconnected-(U$1-Pad52)") (class "Default")
      (node (ref "U$1") (pin "52") (pinfunction "52_52") (pintype "passive"))
    )
    (net (code "222") (name "unconnected-(U$1-Pad53)") (class "Default")
      (node (ref "U$1") (pin "53") (pinfunction "53_53") (pintype "passive"))
    )
    (net (code "223") (name "unconnected-(U$1-Pad54)") (class "Default")
      (node (ref "U$1") (pin "54") (pinfunction "54_54") (pintype "passive"))
    )
    (net (code "224") (name "unconnected-(U$1-Pad55)") (class "Default")
      (node (ref "U$1") (pin "55") (pinfunction "55_55") (pintype "passive"))
    )
    (net (code "225") (name "unconnected-(U$1-Pad56)") (class "Default")
      (node (ref "U$1") (pin "56") (pinfunction "56_56") (pintype "passive"))
    )
    (net (code "226") (name "unconnected-(U$1-Pad57)") (class "Default")
      (node (ref "U$1") (pin "57") (pinfunction "57_57") (pintype "passive"))
    )
    (net (code "227") (name "unconnected-(U$1-Pad58)") (class "Default")
      (node (ref "U$1") (pin "58") (pinfunction "58_58") (pintype "passive"))
    )
    (net (code "228") (name "unconnected-(U$1-Pad59)") (class "Default")
      (node (ref "U$1") (pin "59") (pinfunction "59_59") (pintype "passive"))
    )
    (net (code "229") (name "unconnected-(U$1-Pad60)") (class "Default")
      (node (ref "U$1") (pin "60") (pinfunction "60_60") (pintype "passive"))
    )
    (net (code "230") (name "unconnected-(U$1-Pad61)") (class "Default")
      (node (ref "U$1") (pin "61") (pinfunction "61_61") (pintype "passive"))
    )
    (net (code "231") (name "unconnected-(U$1-Pad62)") (class "Default")
      (node (ref "U$1") (pin "62") (pinfunction "62_62") (pintype "passive"))
    )
    (net (code "232") (name "unconnected-(U$1-Pad63)") (class "Default")
      (node (ref "U$1") (pin "63") (pinfunction "63_63") (pintype "passive"))
    )
    (net (code "233") (name "unconnected-(U$1-VSS-Pad1)") (class "Default")
      (node (ref "U$1") (pin "1") (pinfunction "VSS_1") (pintype "passive"))
    )
    (net (code "234") (name "unconnected-(U$1-XTAL-Pad2)") (class "Default")
      (node (ref "U$1") (pin "2") (pinfunction "XTAL_2") (pintype "passive"))
    )
    (net (code "235") (name "unconnected-(U$5-Pad1)") (class "Default")
      (node (ref "U$5") (pin "1") (pinfunction "1_1") (pintype "passive"))
    )
    (net (code "236") (name "unconnected-(U$5-Pad2)") (class "Default")
      (node (ref "U$5") (pin "2") (pinfunction "2_2") (pintype "passive"))
    )
    (net (code "237") (name "unconnected-(U$6-O-Pad1)") (class "Default")
      (node (ref "U$6") (pin "1") (pinfunction "O_1") (pintype "passive"))
    )
    (net (code "238") (name "unconnected-(U$6-P-Pad2)") (class "Default")
      (node (ref "U$6") (pin "2") (pinfunction "P_2") (pintype "passive"))
    )
    (net (code "239") (name "unconnected-(U2-DCD-Pad10)") (class "Default")
      (node (ref "U2") (pin "10") (pinfunction "DCD_10") (pintype "input"))
    )
    (net (code "240") (name "unconnected-(U2-DSR-Pad9)") (class "Default")
      (node (ref "U2") (pin "9") (pinfunction "DSR_9") (pintype "input"))
    )
    (net (code "241") (name "unconnected-(U2-DTR-Pad2)") (class "Default")
      (node (ref "U2") (pin "2") (pinfunction "DTR_2") (pintype "output"))
    )
    (net (code "242") (name "unconnected-(U2-OSCI-Pad27)") (class "Default")
      (node (ref "U2") (pin "27") (pinfunction "OSCI_27") (pintype "input"))
    )
    (net (code "243") (name "unconnected-(U2-OSCO-Pad28)") (class "Default")
      (node (ref "U2") (pin "28") (pinfunction "OSCO_28") (pintype "output"))
    )
    (net (code "244") (name "unconnected-(U2-PWREN-Pad14)") (class "Default")
      (node (ref "U2") (pin "14") (pinfunction "PWREN_14") (pintype "input"))
    )
    (net (code "245") (name "unconnected-(U2-RESET-Pad19)") (class "Default")
      (node (ref "U2") (pin "19") (pinfunction "RESET_19") (pintype "input"))
    )
    (net (code "246") (name "unconnected-(U2-RI-Pad6)") (class "Default")
      (node (ref "U2") (pin "6") (pinfunction "RI_6") (pintype "input"))
    )
    (net (code "247") (name "unconnected-(U2-RTS-Pad3)") (class "Default")
      (node (ref "U2") (pin "3") (pinfunction "RTS_3") (pintype "output"))
    )
    (net (code "248") (name "unconnected-(U2-RXLED-Pad22)") (class "Default")
      (node (ref "U2") (pin "22") (pinfunction "RXLED_22") (pintype "input"))
    )
    (net (code "249") (name "unconnected-(U2-SLEEP-Pad12)") (class "Default")
      (node (ref "U2") (pin "12") (pinfunction "SLEEP_12") (pintype "input"))
    )
    (net (code "250") (name "unconnected-(U2-TXDEN-Pad13)") (class "Default")
      (node (ref "U2") (pin "13") (pinfunction "TXDEN_13") (pintype "input"))
    )
    (net (code "251") (name "unconnected-(U2-TXLED-Pad23)") (class "Default")
      (node (ref "U2") (pin "23") (pinfunction "TXLED_23") (pintype "input"))
    )
    (net (code "252") (name "unconnected-(X1B-F-Pad10)") (class "Default")
      (node (ref "X1") (pin "10") (pinfunction "F_10") (pintype "passive"))
    )
    (net (code "253") (name "unconnected-(X1C-F-Pad11)") (class "Default")
      (node (ref "X1") (pin "11") (pinfunction "F_11") (pintype "passive"))
    )
    (net (code "254") (name "unconnected-(X1D-F-Pad12)") (class "Default")
      (node (ref "X1") (pin "12") (pinfunction "F_12") (pintype "passive"))
    )
    (net (code "255") (name "unconnected-(X1E-F-Pad13)") (class "Default")
      (node (ref "X1") (pin "13") (pinfunction "F_13") (pintype "passive"))
    )
    (net (code "256") (name "unconnected-(X1F-F-Pad14)") (class "Default")
      (node (ref "X1") (pin "14") (pinfunction "F_14") (pintype "passive"))
    )
    (net (code "257") (name "unconnected-(X1G-F-Pad15)") (class "Default")
      (node (ref "X1") (pin "15") (pinfunction "F_15") (pintype "passive"))
    )
    (net (code "258") (name "unconnected-(X1J-F-Pad4)") (class "Default")
      (node (ref "X1") (pin "4") (pinfunction "F_4") (pintype "passive"))
    )
    (net (code "259") (name "unconnected-(X1K-F-Pad5)") (class "Default")
      (node (ref "X1") (pin "5") (pinfunction "F_5") (pintype "passive"))
    )
    (net (code "260") (name "unconnected-(X1L-F-Pad6)") (class "Default")
      (node (ref "X1") (pin "6") (pinfunction "F_6") (pintype "passive"))
    )
    (net (code "261") (name "unconnected-(X1M-F-Pad7)") (class "Default")
      (node (ref "X1") (pin "7") (pinfunction "F_7") (pintype "passive"))
    )
    (net (code "262") (name "unconnected-(X1N-F-Pad8)") (class "Default")
      (node (ref "X1") (pin "8") (pinfunction "F_8") (pintype "passive"))
    )
    (net (code "263") (name "unconnected-(X1O-F-Pad9)") (class "Default")
      (node (ref "X1") (pin "9") (pinfunction "F_9") (pintype "passive"))
    )
    (net (code "264") (name "unconnected-(X3-Pad1)") (class "Default")
      (node (ref "X3") (pin "1") (pinfunction "1_1") (pintype "passive"))
    )
    (net (code "265") (name "unconnected-(X3-Pad2)") (class "Default")
      (node (ref "X3") (pin "2") (pinfunction "2_2") (pintype "passive"))
    )
    (net (code "266") (name "unconnected-(X3-Pad3)") (class "Default")
      (node (ref "X3") (pin "3") (pinfunction "3_3") (pintype "passive"))
    )
    (net (code "267") (name "unconnected-(X3-Pad4)") (class "Default")
      (node (ref "X3") (pin "4") (pinfunction "4_4") (pintype "passive"))
    )
    (net (code "268") (name "unconnected-(X3-Pad5)") (class "Default")
      (node (ref "X3") (pin "5") (pinfunction "5_5") (pintype "passive"))
    )
    (net (code "269") (name "unconnected-(X3-Pad6)") (class "Default")
      (node (ref "X3") (pin "6") (pinfunction "6_6") (pintype "passive"))
    )
    (net (code "270") (name "unconnected-(X4-Pad2)") (class "Default")
      (node (ref "X4") (pin "2") (pinfunction "2_2") (pintype "passive"))
    )
    (net (code "271") (name "unconnected-(X4-Pad6)") (class "Default")
      (node (ref "X4") (pin "6") (pinfunction "6_6") (pintype "passive"))
    )
    (net (code "272") (name "unconnected-(X5C-F-Pad11)") (class "Default")
      (node (ref "X5") (pin "11") (pinfunction "F_11") (pintype "passive"))
    )
    (net (code "273") (name "unconnected-(X5D-F-Pad12)") (class "Default")
      (node (ref "X5") (pin "12") (pinfunction "F_12") (pintype "passive"))
    )
    (net (code "274") (name "unconnected-(X5G-F-Pad15)") (class "Default")
      (node (ref "X5") (pin "15") (pinfunction "F_15") (pintype "passive"))
    )
    (net (code "275") (name "unconnected-(X5J-F-Pad4)") (class "Default")
      (node (ref "X5") (pin "4") (pinfunction "F_4") (pintype "passive"))
    )
    (net (code "276") (name "unconnected-(X5O-F-Pad9)") (class "Default")
      (node (ref "X5") (pin "9") (pinfunction "F_9") (pintype "passive"))
    )
    (net (code "277") (name "unconnected-(X6K-F-Pad5)") (class "Default")
      (node (ref "X6") (pin "5") (pinfunction "F_5") (pintype "passive"))
    )
    (net (code "278") (name "unconnected-(X6M-F-Pad7)") (class "Default")
      (node (ref "X6") (pin "7") (pinfunction "F_7") (pintype "passive"))
    )
    (net (code "279") (name "unconnected-(X6O-F-Pad9)") (class "Default")
      (node (ref "X6") (pin "9") (pinfunction "F_9") (pintype "passive"))
    )
  )
)
